# citizen_science_flora.net
KiCad netlist of a schematic drawn in EAGLE
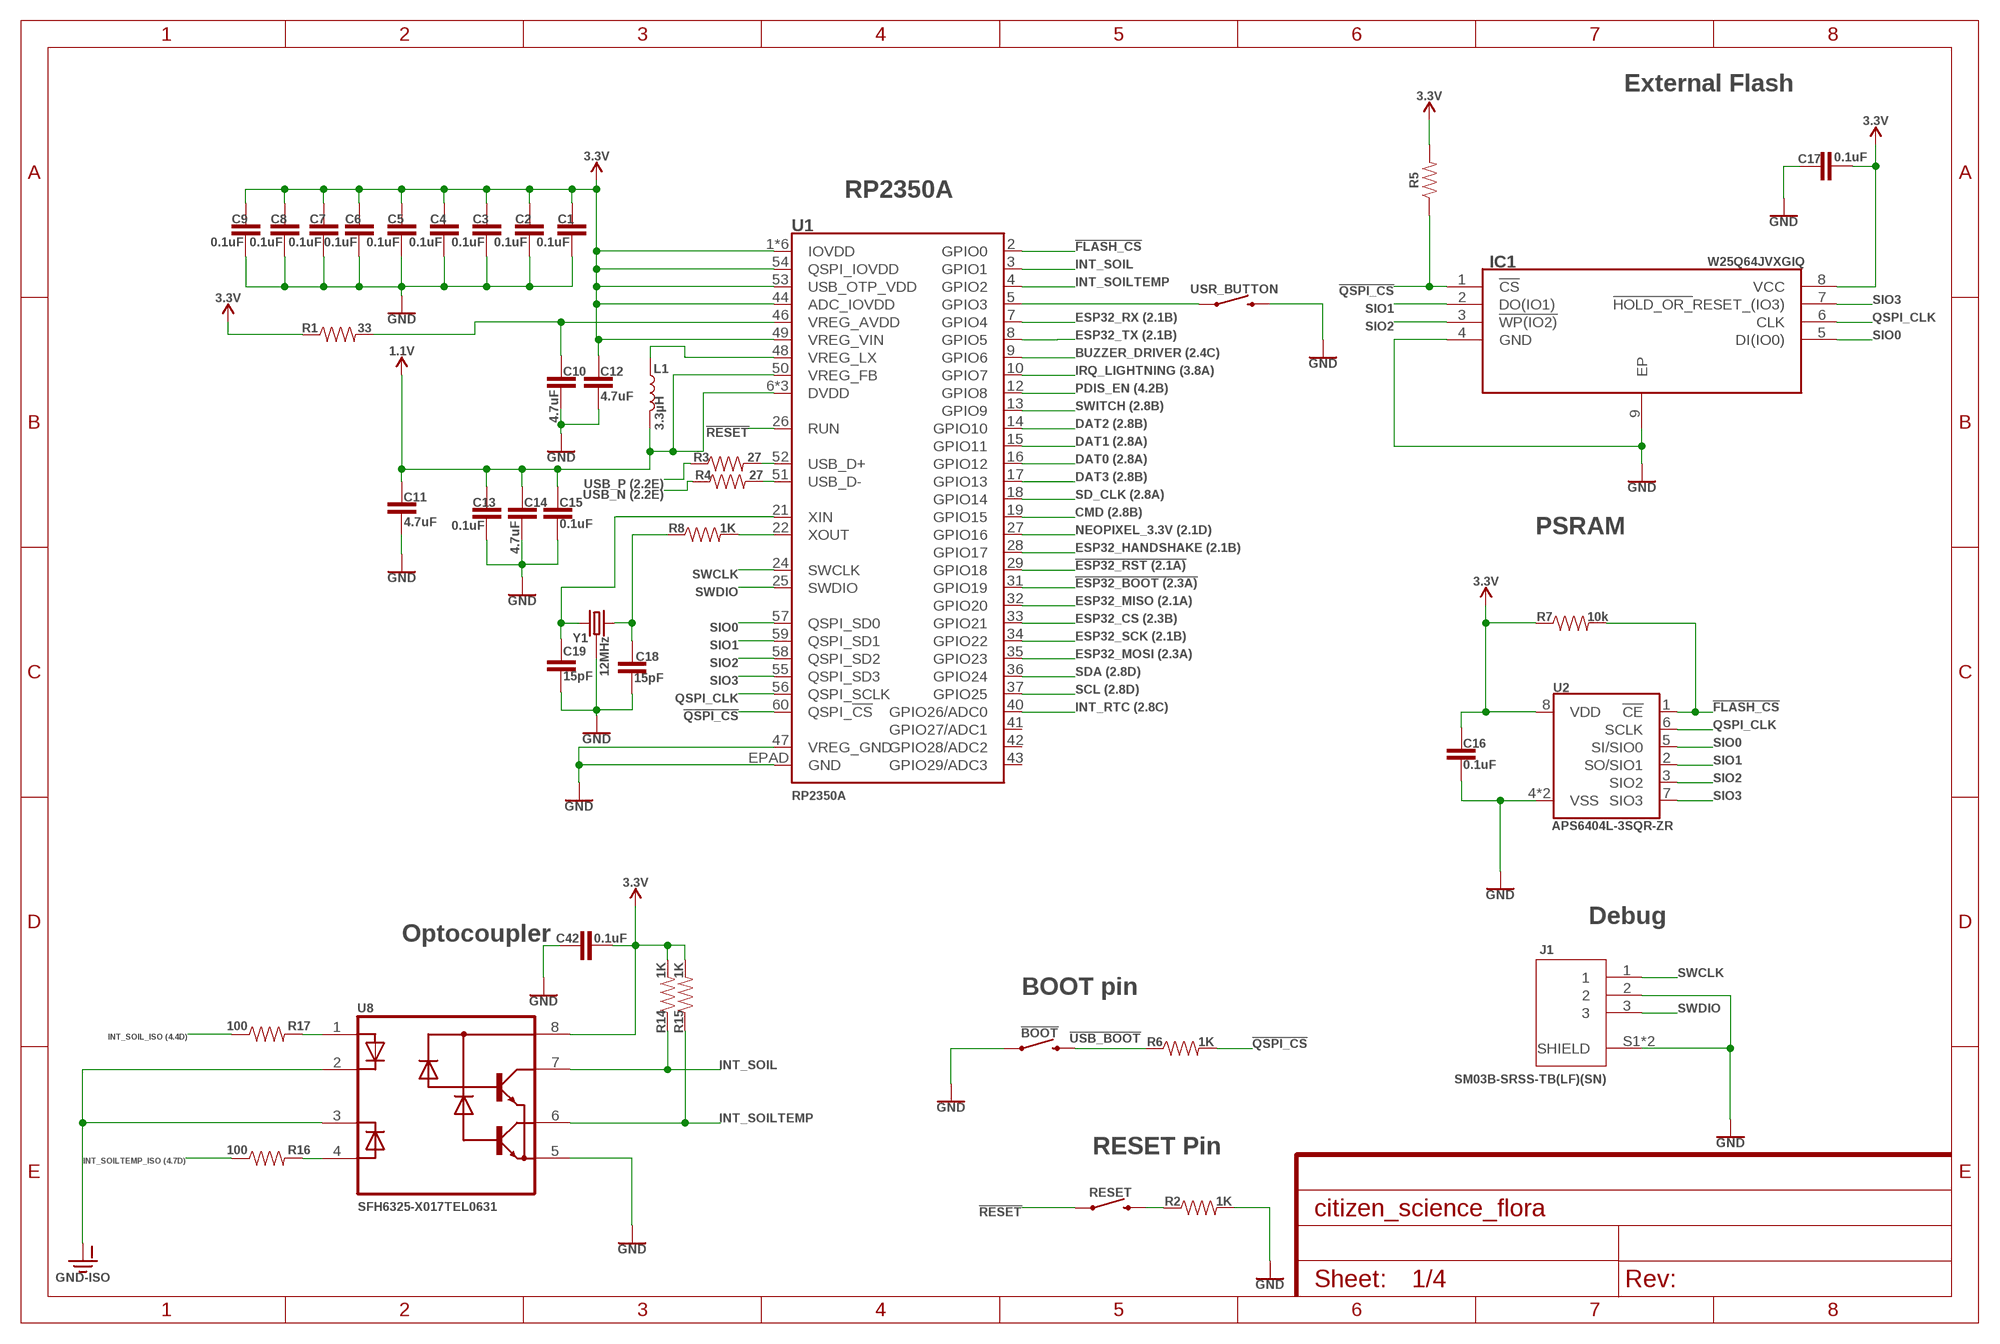
[diagram p0: schematic, sheet 1]
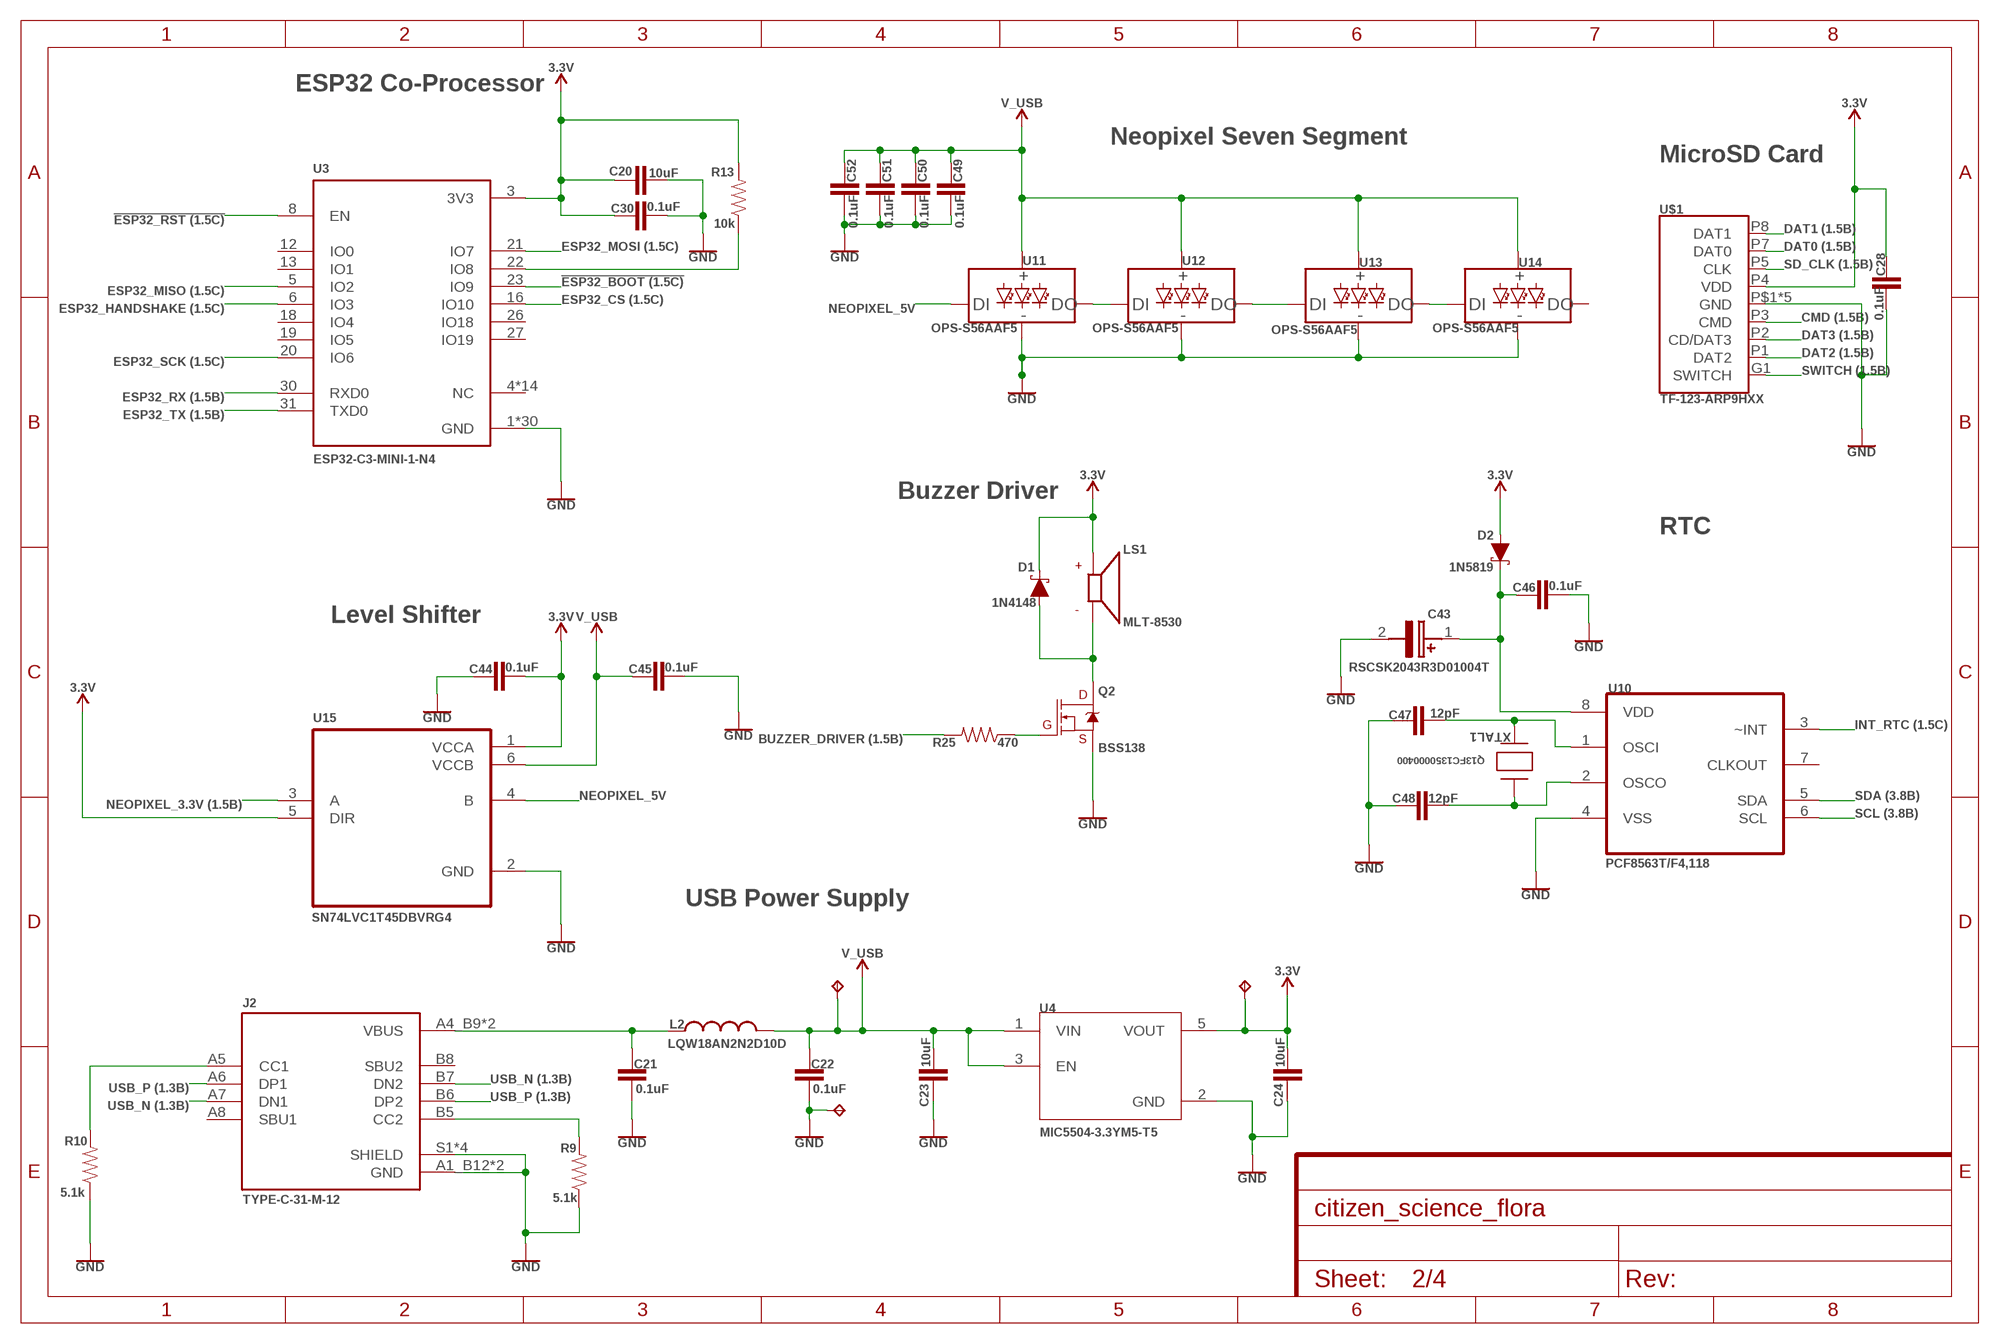
[diagram p1: schematic, sheet 2]
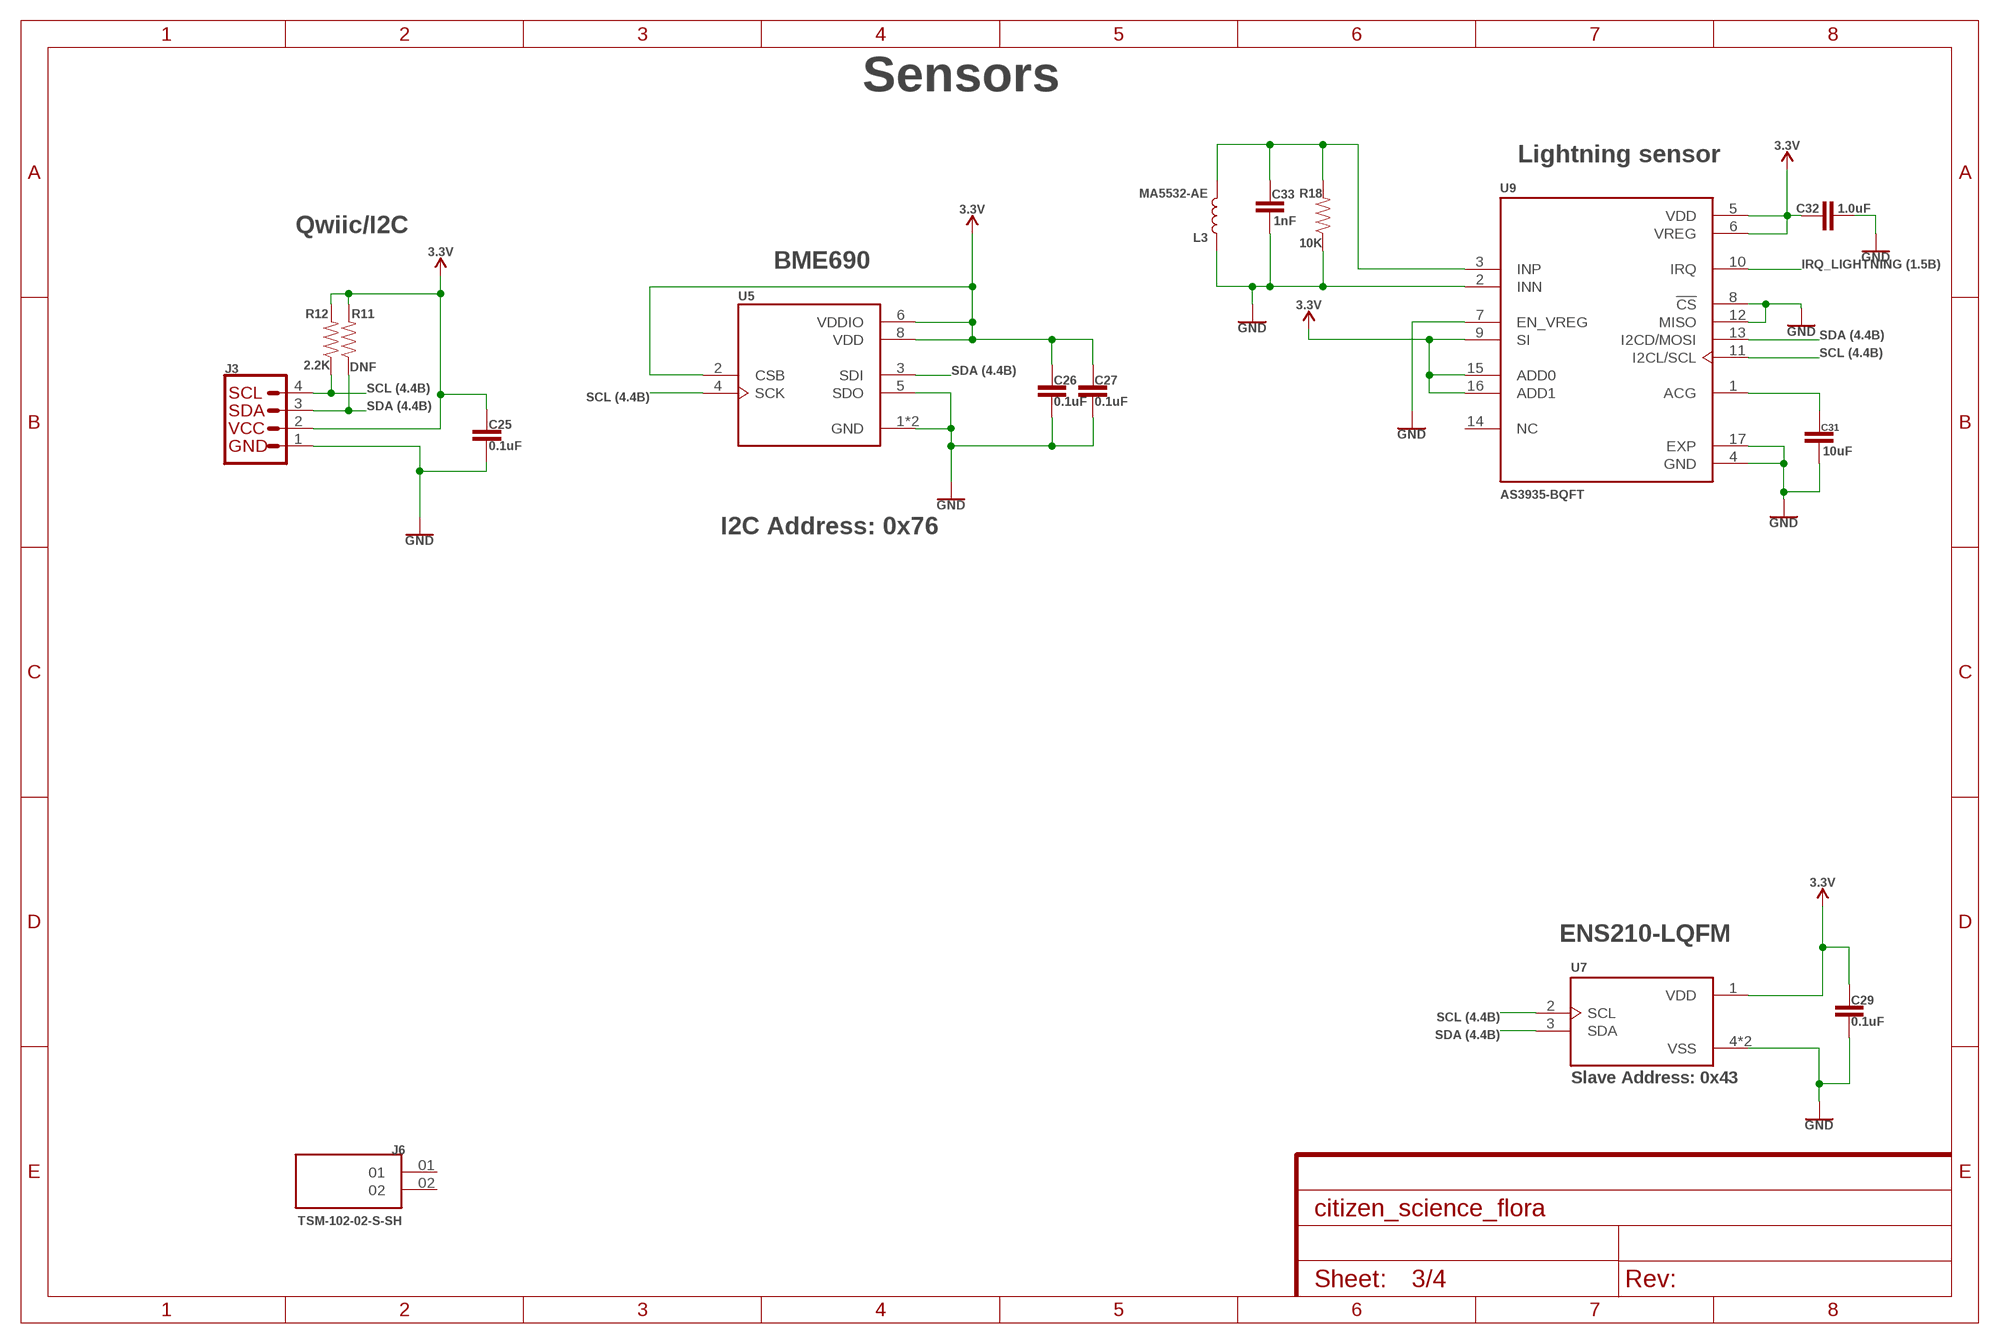
[diagram p2: schematic, sheet 3]
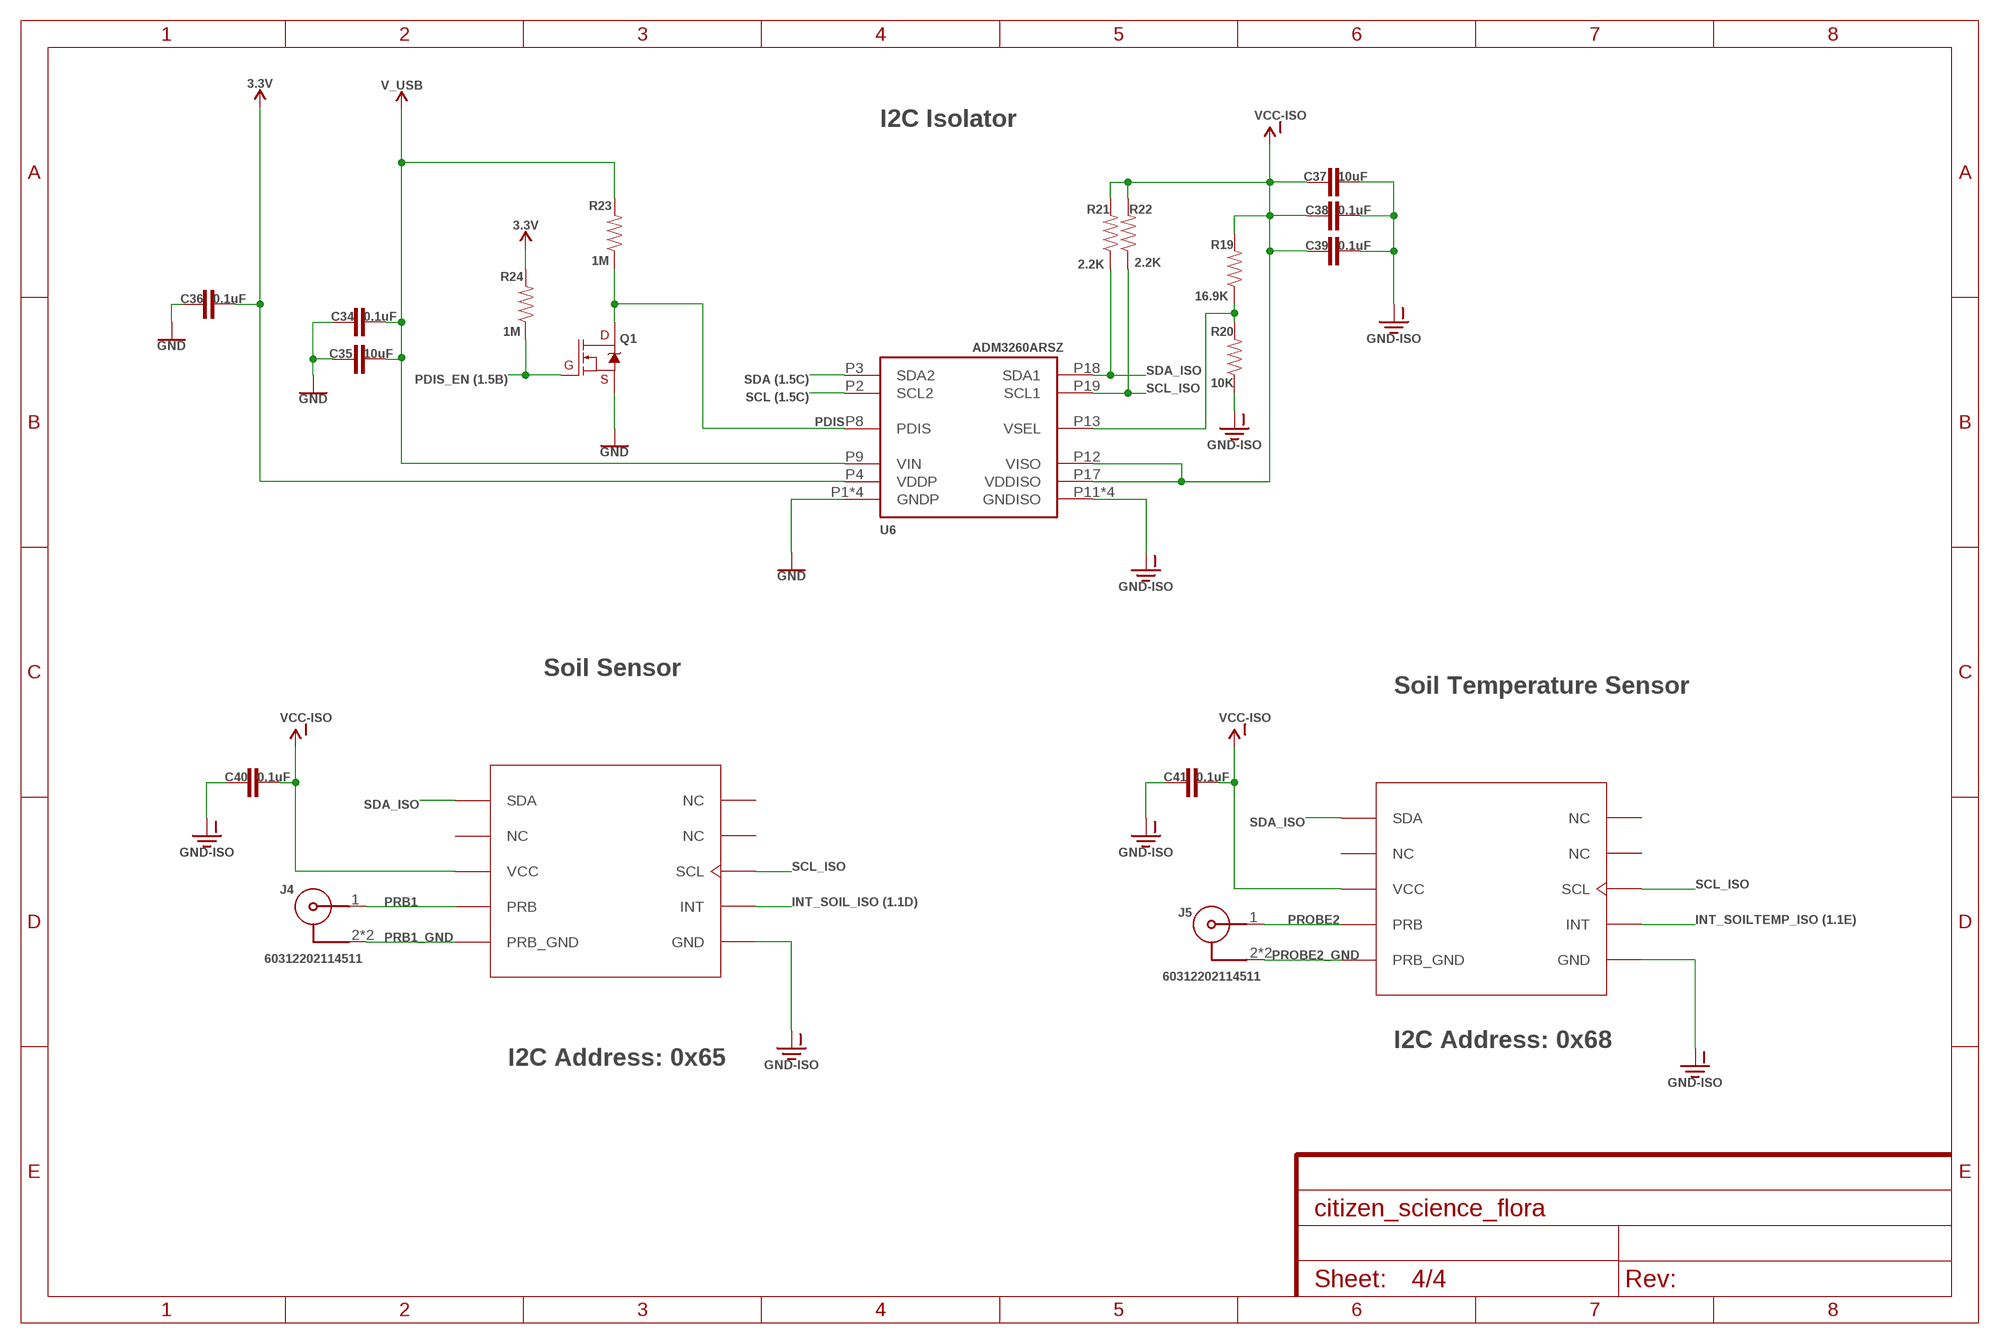
[diagram p3: schematic, sheet 4]

(export (version "E")
  (design (tool "Eeschema 10.0.6"))
  (components
    (comp (ref "!BOOT")
      (value "MOMENTARY-SWITCH-SPST-SMD-4.6X2.8MM")
      (footprint "eagle-import:TACTILE_SWITCH_SMD_4.6X2.8MM")
      (libsource (lib "eagle-import") (part "MOMENTARY-SWITCH-SPST-SMD-4.6X2.8MM"))
    )
    (comp (ref "C1")
      (value "0.1uF")
      (footprint "eagle-import:0402-TIGHT")
      (libsource (lib "eagle-import") (part "0.1UF-0402T-16V-10%-X7R-WE"))
    )
    (comp (ref "C2")
      (value "0.1uF")
      (footprint "eagle-import:0402-TIGHT")
      (libsource (lib "eagle-import") (part "0.1UF-0402T-16V-10%-X7R-WE"))
    )
    (comp (ref "C3")
      (value "0.1uF")
      (footprint "eagle-import:0402-TIGHT")
      (libsource (lib "eagle-import") (part "0.1UF-0402T-16V-10%-X7R-WE"))
    )
    (comp (ref "C4")
      (value "0.1uF")
      (footprint "eagle-import:0402-TIGHT")
      (libsource (lib "eagle-import") (part "0.1UF-0402T-16V-10%-X7R-WE"))
    )
    (comp (ref "C5")
      (value "0.1uF")
      (footprint "eagle-import:0402-TIGHT")
      (libsource (lib "eagle-import") (part "0.1UF-0402T-16V-10%-X7R-WE"))
    )
    (comp (ref "C6")
      (value "0.1uF")
      (footprint "eagle-import:0402-TIGHT")
      (libsource (lib "eagle-import") (part "0.1UF-0402T-16V-10%-X7R-WE"))
    )
    (comp (ref "C7")
      (value "0.1uF")
      (footprint "eagle-import:0402-TIGHT")
      (libsource (lib "eagle-import") (part "0.1UF-0402T-16V-10%-X7R-WE"))
    )
    (comp (ref "C8")
      (value "0.1uF")
      (footprint "eagle-import:0402-TIGHT")
      (libsource (lib "eagle-import") (part "0.1UF-0402T-16V-10%-X7R-WE"))
    )
    (comp (ref "C9")
      (value "0.1uF")
      (footprint "eagle-import:0402-TIGHT")
      (libsource (lib "eagle-import") (part "0.1UF-0402T-16V-10%-X7R-WE"))
    )
    (comp (ref "C10")
      (value "4.7uF")
      (footprint "eagle-import:0402-TIGHT")
      (libsource (lib "eagle-import") (part "4.7UF-0402_TIGHT-6.3V-20%-X5R"))
    )
    (comp (ref "C11")
      (value "4.7uF")
      (footprint "eagle-import:0402-TIGHT")
      (libsource (lib "eagle-import") (part "4.7UF-0402_TIGHT-6.3V-20%-X5R"))
    )
    (comp (ref "C12")
      (value "4.7uF")
      (footprint "eagle-import:0402-TIGHT")
      (libsource (lib "eagle-import") (part "4.7UF-0402_TIGHT-6.3V-20%-X5R"))
    )
    (comp (ref "C13")
      (value "0.1uF")
      (footprint "eagle-import:0402-TIGHT")
      (libsource (lib "eagle-import") (part "0.1UF-0402T-16V-10%-X7R-WE"))
    )
    (comp (ref "C14")
      (value "4.7uF")
      (footprint "eagle-import:0402-TIGHT")
      (libsource (lib "eagle-import") (part "4.7UF-0402_TIGHT-6.3V-20%-X5R"))
    )
    (comp (ref "C15")
      (value "0.1uF")
      (footprint "eagle-import:0402-TIGHT")
      (libsource (lib "eagle-import") (part "0.1UF-0402T-16V-10%-X7R-WE"))
    )
    (comp (ref "C16")
      (value "0.1uF")
      (footprint "eagle-import:0402-TIGHT")
      (libsource (lib "eagle-import") (part "0.1UF-0402T-16V-10%-X7R-WE"))
    )
    (comp (ref "C17")
      (value "0.1uF")
      (footprint "eagle-import:0402-TIGHT")
      (libsource (lib "eagle-import") (part "0.1UF-0402T-16V-10%-X7R-WE"))
    )
    (comp (ref "C18")
      (value "15pF")
      (footprint "eagle-import:0402")
      (libsource (lib "eagle-import") (part "15PF-0402-50V-5%"))
    )
    (comp (ref "C19")
      (value "15pF")
      (footprint "eagle-import:0402")
      (libsource (lib "eagle-import") (part "15PF-0402-50V-5%"))
    )
    (comp (ref "C42")
      (value "0.1uF")
      (footprint "eagle-import:0402-TIGHT")
      (libsource (lib "eagle-import") (part "0.1UF-0402T-16V-10%-X7R-WE"))
    )
    (comp (ref "IC1")
      (value "W25Q64JVXGIQ")
      (footprint "eagle-import:SON80P400X400X50-9N")
      (libsource (lib "eagle-import") (part "W25Q64JVXGIQ"))
    )
    (comp (ref "J1")
      (value "SM03B-SRSS-TB(LF)(SN)")
      (footprint "eagle-import:JST_SM03B-SRSS-TB(LF)(SN)")
      (fields (field (name "MF") "JST Sales America Inc."))
      (libsource (lib "eagle-import") (part "SM03B-SRSS-TB(LF)(SN)"))
    )
    (comp (ref "L1")
      (value "3.3µH")
      (footprint "eagle-import:0805")
      (libsource (lib "eagle-import") (part "INDUCTOR-0805-3.3UH"))
    )
    (comp (ref "R1")
      (value "33")
      (footprint "eagle-import:0402")
      (libsource (lib "eagle-import") (part "33OHM-0402-1/10W-1%"))
    )
    (comp (ref "R2")
      (value "1K")
      (footprint "eagle-import:0402")
      (libsource (lib "eagle-import") (part "1KOHM-0402-1/16W-1%"))
    )
    (comp (ref "R3")
      (value "27")
      (footprint "eagle-import:0402-TIGHT")
      (libsource (lib "eagle-import") (part "27OHM"))
    )
    (comp (ref "R4")
      (value "27")
      (footprint "eagle-import:0402-TIGHT")
      (libsource (lib "eagle-import") (part "27OHM"))
    )
    (comp (ref "R5")
      (value "RESISTOR0402")
      (footprint "eagle-import:0402")
      (libsource (lib "eagle-import") (part "RESISTOR0402"))
    )
    (comp (ref "R6")
      (value "1K")
      (footprint "eagle-import:0402")
      (libsource (lib "eagle-import") (part "1KOHM-0402-1/16W-1%"))
    )
    (comp (ref "R7")
      (value "10k")
      (footprint "eagle-import:0402")
      (libsource (lib "eagle-import") (part "10KOHM-0402-1/16W-1%"))
    )
    (comp (ref "R8")
      (value "1K")
      (footprint "eagle-import:0402")
      (libsource (lib "eagle-import") (part "1KOHM-0402-1/16W-1%"))
    )
    (comp (ref "R14")
      (value "1K")
      (footprint "eagle-import:0402")
      (libsource (lib "eagle-import") (part "1KOHM-0402-1/16W-1%"))
    )
    (comp (ref "R15")
      (value "1K")
      (footprint "eagle-import:0402")
      (libsource (lib "eagle-import") (part "1KOHM-0402-1/16W-1%"))
    )
    (comp (ref "R16")
      (value "100")
      (footprint "eagle-import:0402-TIGHT")
      (libsource (lib "eagle-import") (part "100OHM-0402-TIGHT-1/16W-1%"))
    )
    (comp (ref "R17")
      (value "100")
      (footprint "eagle-import:0402-TIGHT")
      (libsource (lib "eagle-import") (part "100OHM-0402-TIGHT-1/16W-1%"))
    )
    (comp (ref "RESET")
      (value "MOMENTARY-SWITCH-SPST-SMD-4.6X2.8MM")
      (footprint "eagle-import:TACTILE_SWITCH_SMD_4.6X2.8MM")
      (libsource (lib "eagle-import") (part "MOMENTARY-SWITCH-SPST-SMD-4.6X2.8MM"))
    )
    (comp (ref "U1")
      (value "RP2350A")
      (footprint "eagle-import:RP2350A")
      (libsource (lib "eagle-import") (part "RP2350A"))
    )
    (comp (ref "U2")
      (value "APS6404L-3SQR-ZR")
      (footprint "eagle-import:APS6404L-3SQR-ZR")
      (libsource (lib "eagle-import") (part "APS6404L-3SQR-ZR"))
    )
    (comp (ref "U8")
      (value "SFH6325-X017TEL0631")
      (footprint "eagle-import:SOIC127P599X175-8N")
      (libsource (lib "eagle-import") (part "SFH6325-X017TEL0631"))
    )
    (comp (ref "USR_BUTTON")
      (value "MOMENTARY-SWITCH-SPST-SMD-4.6X2.8MM")
      (footprint "eagle-import:TACTILE_SWITCH_SMD_4.6X2.8MM")
      (libsource (lib "eagle-import") (part "MOMENTARY-SWITCH-SPST-SMD-4.6X2.8MM"))
    )
    (comp (ref "Y1")
      (value "12MHz")
      (footprint "eagle-import:CRYSTAL-SMD-3.2X2.5MM")
      (libsource (lib "eagle-import") (part "CRYSTAL-GROUNDEDSMD-3.2X2.5"))
    )
    (comp (ref "C34")
      (value "0.1uF")
      (footprint "eagle-import:0402-TIGHT")
      (libsource (lib "eagle-import") (part "0.1UF-0402T-16V-10%-X7R-WE"))
    )
    (comp (ref "C35")
      (value "10uF")
      (footprint "eagle-import:0402-TIGHT")
      (libsource (lib "eagle-import") (part "10UF-0402T-6.3V-20%"))
    )
    (comp (ref "C36")
      (value "0.1uF")
      (footprint "eagle-import:0402-TIGHT")
      (libsource (lib "eagle-import") (part "0.1UF-0402T-16V-10%-X7R-WE"))
    )
    (comp (ref "C37")
      (value "10uF")
      (footprint "eagle-import:0402-TIGHT")
      (libsource (lib "eagle-import") (part "10UF-0402T-6.3V-20%"))
    )
    (comp (ref "C38")
      (value "0.1uF")
      (footprint "eagle-import:0402-TIGHT")
      (libsource (lib "eagle-import") (part "0.1UF-0402T-16V-10%-X7R-WE"))
    )
    (comp (ref "C39")
      (value "0.1uF")
      (footprint "eagle-import:0402-TIGHT")
      (libsource (lib "eagle-import") (part "0.1UF-0402T-16V-10%-X7R-WE"))
    )
    (comp (ref "C40")
      (value "0.1uF")
      (footprint "eagle-import:0402-TIGHT")
      (libsource (lib "eagle-import") (part "0.1UF-0402T-16V-10%-X7R-WE"))
    )
    (comp (ref "C41")
      (value "0.1uF")
      (footprint "eagle-import:0402-TIGHT")
      (libsource (lib "eagle-import") (part "0.1UF-0402T-16V-10%-X7R-WE"))
    )
    (comp (ref "J4")
      (value "60312202114511")
      (footprint "eagle-import:60312202114511")
      (fields (field (name "MF") "Wurth Electronics"))
      (libsource (lib "eagle-import") (part "60312202114511"))
    )
    (comp (ref "J5")
      (value "60312202114511")
      (footprint "eagle-import:60312202114511")
      (fields (field (name "MF") "Wurth Electronics"))
      (libsource (lib "eagle-import") (part "60312202114511"))
    )
    (comp (ref "Q1")
      (value "220mA/50V/3.5Ω")
      (footprint "eagle-import:SOT23-3")
      (libsource (lib "eagle-import") (part "MOSFET-NCH-BSS138"))
    )
    (comp (ref "R19")
      (value "16.9K")
      (footprint "eagle-import:0402")
      (libsource (lib "eagle-import") (part "RESISTOR0402"))
    )
    (comp (ref "R20")
      (value "10K")
      (footprint "eagle-import:0402-TIGHT")
      (libsource (lib "eagle-import") (part "10KOHM-0402-1/10W-0.1%"))
    )
    (comp (ref "R21")
      (value "2.2K")
      (footprint "eagle-import:0402")
      (libsource (lib "eagle-import") (part "2.2KOHM-0402-1/16W-1%"))
    )
    (comp (ref "R22")
      (value "2.2K")
      (footprint "eagle-import:0402")
      (libsource (lib "eagle-import") (part "2.2KOHM-0402-1/16W-1%"))
    )
    (comp (ref "R23")
      (value "1M")
      (footprint "eagle-import:0402")
      (libsource (lib "eagle-import") (part "1MOHM-0402-1/16W-5%"))
    )
    (comp (ref "R24")
      (value "1M")
      (footprint "eagle-import:0402")
      (libsource (lib "eagle-import") (part "1MOHM-0402-1/16W-5%"))
    )
    (comp (ref "U$2")
      (value "PH-OEM")
      (footprint "eagle-import:PH_SENSOR")
      (libsource (lib "eagle-import") (part "PH-OEM"))
    )
    (comp (ref "U$3")
      (value "PH-OEM")
      (footprint "eagle-import:PH_SENSOR")
      (libsource (lib "eagle-import") (part "PH-OEM"))
    )
    (comp (ref "U6")
      (value "ADM3260ARSZ")
      (footprint "eagle-import:SSOP20")
      (fields (field (name "MF") "Analog Devices"))
      (libsource (lib "eagle-import") (part "ADM3260ARSZ"))
    )
    (comp (ref "3.3V")
      (value "TPB1,27")
      (footprint "eagle-import:B1,27")
      (libsource (lib "eagle-import") (part "TPB1,27"))
    )
    (comp (ref "C20")
      (value "10uF")
      (footprint "eagle-import:0402-TIGHT")
      (libsource (lib "eagle-import") (part "10UF-0402T-6.3V-20%"))
    )
    (comp (ref "C21")
      (value "0.1uF")
      (footprint "eagle-import:0402")
      (libsource (lib "eagle-import") (part "0.1UF-0402-6.3V-10%-X7R"))
    )
    (comp (ref "C22")
      (value "0.1uF")
      (footprint "eagle-import:0402")
      (libsource (lib "eagle-import") (part "0.1UF-0402-6.3V-10%-X7R"))
    )
    (comp (ref "C23")
      (value "10uF")
      (footprint "eagle-import:0402-TIGHT")
      (libsource (lib "eagle-import") (part "10UF-0402T-6.3V-20%"))
    )
    (comp (ref "C24")
      (value "10uF")
      (footprint "eagle-import:0402-TIGHT")
      (libsource (lib "eagle-import") (part "10UF-0402T-6.3V-20%"))
    )
    (comp (ref "C28")
      (value "0.1uF")
      (footprint "eagle-import:0402-TIGHT")
      (libsource (lib "eagle-import") (part "0.1UF-0402T-16V-10%-X7R-WE"))
    )
    (comp (ref "C30")
      (value "0.1uF")
      (footprint "eagle-import:0402")
      (libsource (lib "eagle-import") (part "0.1UF-0402-6.3V-10%-X7R"))
    )
    (comp (ref "C43")
      (value "RSCSK2043R3D01004T")
      (footprint "eagle-import:RSCSK2043R3D01004T")
      (fields (field (name "MOUSER_PART_NUMBER") "555-DSK3R3H204T614H2"))
      (libsource (lib "eagle-import") (part "RSCSK2043R3D01004T"))
    )
    (comp (ref "C44")
      (value "0.1uF")
      (footprint "eagle-import:0402")
      (libsource (lib "eagle-import") (part "0.1UF-0402-6.3V-10%-X7R"))
    )
    (comp (ref "C45")
      (value "0.1uF")
      (footprint "eagle-import:0402")
      (libsource (lib "eagle-import") (part "0.1UF-0402-6.3V-10%-X7R"))
    )
    (comp (ref "C46")
      (value "0.1uF")
      (footprint "eagle-import:0402")
      (libsource (lib "eagle-import") (part "0.1UF-0402-6.3V-10%-X7R"))
    )
    (comp (ref "C47")
      (value "12pF")
      (footprint "eagle-import:0402")
      (libsource (lib "eagle-import") (part "12PF-0402-50V-5%"))
    )
    (comp (ref "C48")
      (value "12pF")
      (footprint "eagle-import:0402")
      (libsource (lib "eagle-import") (part "12PF-0402-50V-5%"))
    )
    (comp (ref "C49")
      (value "0.1uF")
      (footprint "eagle-import:0402")
      (libsource (lib "eagle-import") (part "0.1UF-0402-6.3V-10%-X7R"))
    )
    (comp (ref "C50")
      (value "0.1uF")
      (footprint "eagle-import:0402")
      (libsource (lib "eagle-import") (part "0.1UF-0402-6.3V-10%-X7R"))
    )
    (comp (ref "C51")
      (value "0.1uF")
      (footprint "eagle-import:0402")
      (libsource (lib "eagle-import") (part "0.1UF-0402-6.3V-10%-X7R"))
    )
    (comp (ref "C52")
      (value "0.1uF")
      (footprint "eagle-import:0402")
      (libsource (lib "eagle-import") (part "0.1UF-0402-6.3V-10%-X7R"))
    )
    (comp (ref "D1")
      (value "1N4148")
      (footprint "eagle-import:SOD-323")
      (libsource (lib "eagle-import") (part "DIODE-SCHOTTKY-BAT60A"))
    )
    (comp (ref "D2")
      (value "1N5819")
      (footprint "eagle-import:SOD-323")
      (libsource (lib "eagle-import") (part "DIODE-SCHOTTKY-BAT20J"))
    )
    (comp (ref "GND")
      (value "TPB1,27")
      (footprint "eagle-import:B1,27")
      (libsource (lib "eagle-import") (part "TPB1,27"))
    )
    (comp (ref "J2")
      (value "TYPE-C-31-M-12")
      (footprint "eagle-import:HRO_TYPE-C-31-M-12")
      (fields (field (name "MF") "HRO Electronics Co., Ltd."))
      (libsource (lib "eagle-import") (part "TYPE-C-31-M-12"))
    )
    (comp (ref "L2")
      (value "LQW18AN2N2D10D")
      (footprint "eagle-import:INDC1608X100N")
      (fields (field (name "MF") "Murata"))
      (libsource (lib "eagle-import") (part "LQW18AN2N2D10D"))
    )
    (comp (ref "LS1")
      (value "MLT-8530")
      (footprint "eagle-import:XDCR_CMT-8504-100-SMT-TR")
      (fields (field (name "MANUFACTURER") "CUI Inc."))
      (libsource (lib "eagle-import") (part "CMT-8504-100-SMT-TR"))
    )
    (comp (ref "Q2")
      (value "BSS138")
      (footprint "eagle-import:SOT323")
      (libsource (lib "eagle-import") (part "MOSFET-NCH-2N7002PW"))
    )
    (comp (ref "R9")
      (value "5.1k")
      (footprint "eagle-import:0402")
      (libsource (lib "eagle-import") (part "5.1KOHM-0402-1/16W-1%"))
    )
    (comp (ref "R10")
      (value "5.1k")
      (footprint "eagle-import:0402")
      (libsource (lib "eagle-import") (part "5.1KOHM-0402-1/16W-1%"))
    )
    (comp (ref "R13")
      (value "10k")
      (footprint "eagle-import:0402")
      (libsource (lib "eagle-import") (part "10KOHM-0402-1/16W-1%"))
    )
    (comp (ref "R25")
      (value "470")
      (footprint "eagle-import:0402")
      (libsource (lib "eagle-import") (part "10KOHM-0402-1/16W-1%"))
    )
    (comp (ref "U$1")
      (value "TF-123-ARP9HXX")
      (footprint "eagle-import:MICROSDCARD")
      (libsource (lib "eagle-import") (part "TF-123-ARP9HXX"))
    )
    (comp (ref "U3")
      (value "ESP32-C3-MINI-1-N4")
      (footprint "eagle-import:XCVR_ESP32-C3-MINI-1-N4")
      (fields (field (name "MF") "Espressif Systems"))
      (libsource (lib "eagle-import") (part "ESP32-C3-MINI-1-N4"))
    )
    (comp (ref "U4")
      (value "MIC5504-3.3YM5-T5")
      (footprint "eagle-import:SOT95P280X145-5N")
      (fields (field (name "MF") "Microchip"))
      (libsource (lib "eagle-import") (part "MIC5504-3.3YM5-T5"))
    )
    (comp (ref "U10")
      (value "PCF8563T/F4,118")
      (footprint "eagle-import:SOIC127P600X175-8N")
      (fields (field (name "MF") "NXP USA"))
      (libsource (lib "eagle-import") (part "PCF8563T/F4,118"))
    )
    (comp (ref "U11")
      (value "OPS-S56AAF5")
      (footprint "eagle-import:OPS-S56AAF5")
      (libsource (lib "eagle-import") (part "OPS-S56AAF5"))
    )
    (comp (ref "U12")
      (value "OPS-S56AAF5")
      (footprint "eagle-import:OPS-S56AAF5")
      (libsource (lib "eagle-import") (part "OPS-S56AAF5"))
    )
    (comp (ref "U13")
      (value "OPS-S56AAF5")
      (footprint "eagle-import:OPS-S56AAF5")
      (libsource (lib "eagle-import") (part "OPS-S56AAF5"))
    )
    (comp (ref "U14")
      (value "OPS-S56AAF5")
      (footprint "eagle-import:OPS-S56AAF5")
      (libsource (lib "eagle-import") (part "OPS-S56AAF5"))
    )
    (comp (ref "U15")
      (value "SN74LVC1T45DBVRG4")
      (footprint "eagle-import:SOT95P280X145-6N")
      (fields (field (name "MF") "Texas Instruments"))
      (libsource (lib "eagle-import") (part "SN74LVC1T45DBVRG4"))
    )
    (comp (ref "USB")
      (value "V_USB")
      (footprint "eagle-import:B1,27")
      (libsource (lib "eagle-import") (part "TPB1,27"))
    )
    (comp (ref "XTAL1")
      (value "Q13FC1350000400")
      (footprint "eagle-import:XTAL_FC-135_EPS")
      (fields (field (name "MF") "EPSON"))
      (libsource (lib "eagle-import") (part "Q13FC1350000400"))
    )
    (comp (ref "C25")
      (value "0.1uF")
      (footprint "eagle-import:0402-TIGHT")
      (libsource (lib "eagle-import") (part "0.1UF-0402T-16V-10%-X7R-WE"))
    )
    (comp (ref "C26")
      (value "0.1uF")
      (footprint "eagle-import:0402-TIGHT")
      (libsource (lib "eagle-import") (part "0.1UF-0402T-16V-10%-X7R-WE"))
    )
    (comp (ref "C27")
      (value "0.1uF")
      (footprint "eagle-import:0402-TIGHT")
      (libsource (lib "eagle-import") (part "0.1UF-0402T-16V-10%-X7R-WE"))
    )
    (comp (ref "C29")
      (value "0.1uF")
      (footprint "eagle-import:0402-TIGHT")
      (libsource (lib "eagle-import") (part "0.1UF-0402T-16V-10%-X7R-WE"))
    )
    (comp (ref "C31")
      (value "10uF")
      (footprint "eagle-import:0402-TIGHT")
      (libsource (lib "eagle-import") (part "10UF-0402T-6.3V-20%"))
    )
    (comp (ref "C32")
      (value "1.0uF")
      (footprint "eagle-import:0402")
      (libsource (lib "eagle-import") (part "1.0UF-0402-16V-10%"))
    )
    (comp (ref "C33")
      (value "1nF")
      (footprint "eagle-import:0402")
      (libsource (lib "eagle-import") (part "1.0NF/1000PF-0402-25V-10%-X7R"))
    )
    (comp (ref "J3")
      (value "QWIIC_CONNECTORJS-1MM")
      (footprint "eagle-import:1X04_1MM_RA")
      (libsource (lib "eagle-import") (part "QWIIC_CONNECTORJS-1MM"))
    )
    (comp (ref "J6")
      (value "TSM-102-02-S-SH")
      (footprint "eagle-import:SAMTEC_TSM-102-02-S-SH")
      (fields (field (name "MF") "Samtec"))
      (libsource (lib "eagle-import") (part "TSM-102-02-S-SH"))
    )
    (comp (ref "L3")
      (value "MA5532-AE")
      (footprint "eagle-import:MA5532-AE")
      (fields (field (name "MF") "Coilcraft"))
      (libsource (lib "eagle-import") (part "MA5532-AE"))
    )
    (comp (ref "R11")
      (value "DNF")
      (footprint "eagle-import:0402")
      (libsource (lib "eagle-import") (part "2.2KOHM-0402-1/16W-1%"))
    )
    (comp (ref "R12")
      (value "2.2K")
      (footprint "eagle-import:0402")
      (libsource (lib "eagle-import") (part "2.2KOHM-0402-1/16W-1%"))
    )
    (comp (ref "R18")
      (value "10K")
      (footprint "eagle-import:0402-TIGHT")
      (libsource (lib "eagle-import") (part "10KOHM-0402-1/10W-0.1%"))
    )
    (comp (ref "U5")
      (value "BME690")
      (footprint "eagle-import:IC_BME688")
      (fields (field (name "MF") "Bosch Sensortec") (field (name "MP") "BME688"))
      (libsource (lib "eagle-import") (part "BME690"))
    )
    (comp (ref "U7")
      (value "ENS210-LQFM")
      (footprint "eagle-import:XDCR_ENS210-LQFM")
      (fields (field (name "MF") "ScioSense"))
      (libsource (lib "eagle-import") (part "ENS210-LQFM"))
    )
    (comp (ref "U9")
      (value "AS3935-BQFT")
      (footprint "eagle-import:QFN65P400X400X80-17N")
      (fields (field (name "MF") "ScioSense"))
      (libsource (lib "eagle-import") (part "AS3935-BQFT"))
    )
  )
  (nets
    (net (code "1") (name "1.1V") (class "Default")
      (node (ref "C11") (pin "1") (pinfunction "1_1") (pintype "passive"))
      (node (ref "C13") (pin "1") (pinfunction "1_1") (pintype "passive"))
      (node (ref "C14") (pin "1") (pinfunction "1_1") (pintype "passive"))
      (node (ref "C15") (pin "1") (pinfunction "1_1") (pintype "passive"))
      (node (ref "L1") (pin "2") (pinfunction "2_2") (pintype "passive"))
      (node (ref "U1") (pin "23") (pinfunction "DVDD_23") (pintype "bidirectional"))
      (node (ref "U1") (pin "39") (pinfunction "DVDD_39") (pintype "bidirectional"))
      (node (ref "U1") (pin "50") (pinfunction "VREG_FB_50") (pintype "bidirectional"))
      (node (ref "U1") (pin "6") (pinfunction "DVDD_6") (pintype "bidirectional"))
    )
    (net (code "2") (name "3.3V") (class "Default")
      (node (ref "3.3V") (pin "TP") (pinfunction "TP_TP") (pintype "input"))
      (node (ref "C1") (pin "1") (pinfunction "1_1") (pintype "passive"))
      (node (ref "C12") (pin "1") (pinfunction "1_1") (pintype "passive"))
      (node (ref "C16") (pin "1") (pinfunction "1_1") (pintype "passive"))
      (node (ref "C17") (pin "2") (pinfunction "2_2") (pintype "passive"))
      (node (ref "C2") (pin "1") (pinfunction "1_1") (pintype "passive"))
      (node (ref "C20") (pin "1") (pinfunction "1_1") (pintype "passive"))
      (node (ref "C24") (pin "2") (pinfunction "2_2") (pintype "passive"))
      (node (ref "C25") (pin "1") (pinfunction "1_1") (pintype "passive"))
      (node (ref "C26") (pin "1") (pinfunction "1_1") (pintype "passive"))
      (node (ref "C27") (pin "1") (pinfunction "1_1") (pintype "passive"))
      (node (ref "C28") (pin "1") (pinfunction "1_1") (pintype "passive"))
      (node (ref "C29") (pin "1") (pinfunction "1_1") (pintype "passive"))
      (node (ref "C3") (pin "1") (pinfunction "1_1") (pintype "passive"))
      (node (ref "C30") (pin "1") (pinfunction "1_1") (pintype "passive"))
      (node (ref "C32") (pin "1") (pinfunction "1_1") (pintype "passive"))
      (node (ref "C36") (pin "2") (pinfunction "2_2") (pintype "passive"))
      (node (ref "C4") (pin "1") (pinfunction "1_1") (pintype "passive"))
      (node (ref "C42") (pin "2") (pinfunction "2_2") (pintype "passive"))
      (node (ref "C44") (pin "2") (pinfunction "2_2") (pintype "passive"))
      (node (ref "C5") (pin "1") (pinfunction "1_1") (pintype "passive"))
      (node (ref "C6") (pin "1") (pinfunction "1_1") (pintype "passive"))
      (node (ref "C7") (pin "1") (pinfunction "1_1") (pintype "passive"))
      (node (ref "C8") (pin "1") (pinfunction "1_1") (pintype "passive"))
      (node (ref "C9") (pin "1") (pinfunction "1_1") (pintype "passive"))
      (node (ref "D1") (pin "C") (pinfunction "C_C") (pintype "passive"))
      (node (ref "D2") (pin "A") (pinfunction "A_A") (pintype "passive"))
      (node (ref "IC1") (pin "8") (pinfunction "VCC_8") (pintype "bidirectional"))
      (node (ref "J3") (pin "2") (pinfunction "2_2") (pintype "power_in"))
      (node (ref "LS1") (pin "P") (pinfunction "P_P") (pintype "passive"))
      (node (ref "R1") (pin "1") (pinfunction "1_1") (pintype "passive"))
      (node (ref "R11") (pin "2") (pinfunction "2_2") (pintype "passive"))
      (node (ref "R12") (pin "2") (pinfunction "2_2") (pintype "passive"))
      (node (ref "R13") (pin "2") (pinfunction "2_2") (pintype "passive"))
      (node (ref "R14") (pin "2") (pinfunction "2_2") (pintype "passive"))
      (node (ref "R15") (pin "2") (pinfunction "2_2") (pintype "passive"))
      (node (ref "R24") (pin "2") (pinfunction "2_2") (pintype "passive"))
      (node (ref "R5") (pin "2") (pinfunction "2_2") (pintype "passive"))
      (node (ref "R7") (pin "1") (pinfunction "1_1") (pintype "passive"))
      (node (ref "U$1") (pin "P4") (pinfunction "VDD_P4") (pintype "power_in"))
      (node (ref "U1") (pin "1") (pinfunction "IOVDD_1") (pintype "bidirectional"))
      (node (ref "U1") (pin "11") (pinfunction "IOVDD_11") (pintype "bidirectional"))
      (node (ref "U1") (pin "20") (pinfunction "IOVDD_20") (pintype "bidirectional"))
      (node (ref "U1") (pin "30") (pinfunction "IOVDD_30") (pintype "bidirectional"))
      (node (ref "U1") (pin "38") (pinfunction "IOVDD_38") (pintype "bidirectional"))
      (node (ref "U1") (pin "44") (pinfunction "ADC_IOVDD_44") (pintype "bidirectional"))
      (node (ref "U1") (pin "45") (pinfunction "IOVDD_45") (pintype "bidirectional"))
      (node (ref "U1") (pin "49") (pinfunction "VREG_VIN_49") (pintype "bidirectional"))
      (node (ref "U1") (pin "53") (pinfunction "USB_OTP_VDD_53") (pintype "bidirectional"))
      (node (ref "U1") (pin "54") (pinfunction "QSPI_IOVDD_54") (pintype "bidirectional"))
      (node (ref "U15") (pin "1") (pinfunction "VCCA_1") (pintype "power_in"))
      (node (ref "U15") (pin "5") (pinfunction "DIR_5") (pintype "input"))
      (node (ref "U2") (pin "8") (pinfunction "VDD_8") (pintype "bidirectional"))
      (node (ref "U3") (pin "3") (pinfunction "3V3_3") (pintype "power_in"))
      (node (ref "U4") (pin "5") (pinfunction "VOUT_5") (pintype "output"))
      (node (ref "U5") (pin "2") (pinfunction "CSB_2") (pintype "input"))
      (node (ref "U5") (pin "6") (pinfunction "VDDIO_6") (pintype "power_in"))
      (node (ref "U5") (pin "8") (pinfunction "VDD_8") (pintype "power_in"))
      (node (ref "U6") (pin "P4") (pinfunction "VDDP_P4") (pintype "bidirectional"))
      (node (ref "U7") (pin "1") (pinfunction "VDD_1") (pintype "power_in"))
      (node (ref "U8") (pin "8") (pinfunction "C(VCC)_8") (pintype "passive"))
      (node (ref "U9") (pin "15") (pinfunction "ADD0_15") (pintype "input"))
      (node (ref "U9") (pin "16") (pinfunction "ADD1_16") (pintype "input"))
      (node (ref "U9") (pin "5") (pinfunction "VDD_5") (pintype "power_in"))
      (node (ref "U9") (pin "6") (pinfunction "VREG_6") (pintype "power_in"))
      (node (ref "U9") (pin "9") (pinfunction "SI_9") (pintype "input"))
    )
    (net (code "3") (name "BUZZER_DRIVER") (class "Default")
      (node (ref "R25") (pin "2") (pinfunction "2_2") (pintype "passive"))
      (node (ref "U1") (pin "9") (pinfunction "GPIO6_9") (pintype "bidirectional"))
    )
    (net (code "4") (name "CMD") (class "Default")
      (node (ref "U$1") (pin "P3") (pinfunction "CMD_P3") (pintype "bidirectional"))
      (node (ref "U1") (pin "19") (pinfunction "GPIO15_19") (pintype "bidirectional"))
    )
    (net (code "5") (name "DAT0") (class "Default")
      (node (ref "U$1") (pin "P7") (pinfunction "DAT0_P7") (pintype "bidirectional"))
      (node (ref "U1") (pin "16") (pinfunction "GPIO12_16") (pintype "bidirectional"))
    )
    (net (code "6") (name "DAT1") (class "Default")
      (node (ref "U$1") (pin "P8") (pinfunction "DAT1_P8") (pintype "bidirectional"))
      (node (ref "U1") (pin "15") (pinfunction "GPIO11_15") (pintype "bidirectional"))
    )
    (net (code "7") (name "DAT2") (class "Default")
      (node (ref "U$1") (pin "P1") (pinfunction "DAT2_P1") (pintype "bidirectional"))
      (node (ref "U1") (pin "14") (pinfunction "GPIO10_14") (pintype "bidirectional"))
    )
    (net (code "8") (name "DAT3") (class "Default")
      (node (ref "U$1") (pin "P2") (pinfunction "CD/DAT3_P2") (pintype "bidirectional"))
      (node (ref "U1") (pin "17") (pinfunction "GPIO13_17") (pintype "bidirectional"))
    )
    (net (code "9") (name "ESP32_CS") (class "Default")
      (node (ref "U1") (pin "33") (pinfunction "GPIO21_33") (pintype "bidirectional"))
      (node (ref "U3") (pin "16") (pinfunction "IO10_16") (pintype "bidirectional"))
    )
    (net (code "10") (name "ESP32_HANDSHAKE") (class "Default")
      (node (ref "U1") (pin "28") (pinfunction "GPIO17_28") (pintype "bidirectional"))
      (node (ref "U3") (pin "6") (pinfunction "IO3_6") (pintype "bidirectional"))
    )
    (net (code "11") (name "ESP32_MISO") (class "Default")
      (node (ref "U1") (pin "32") (pinfunction "GPIO20_32") (pintype "bidirectional"))
      (node (ref "U3") (pin "5") (pinfunction "IO2_5") (pintype "bidirectional"))
    )
    (net (code "12") (name "ESP32_MOSI") (class "Default")
      (node (ref "U1") (pin "35") (pinfunction "GPIO23_35") (pintype "bidirectional"))
      (node (ref "U3") (pin "21") (pinfunction "IO7_21") (pintype "bidirectional"))
    )
    (net (code "13") (name "ESP32_RX") (class "Default")
      (node (ref "U1") (pin "7") (pinfunction "GPIO4_7") (pintype "bidirectional"))
      (node (ref "U3") (pin "30") (pinfunction "RXD0_30") (pintype "bidirectional"))
    )
    (net (code "14") (name "ESP32_SCK") (class "Default")
      (node (ref "U1") (pin "34") (pinfunction "GPIO22_34") (pintype "bidirectional"))
      (node (ref "U3") (pin "20") (pinfunction "IO6_20") (pintype "bidirectional"))
    )
    (net (code "15") (name "ESP32_TX") (class "Default")
      (node (ref "U1") (pin "8") (pinfunction "GPIO5_8") (pintype "bidirectional"))
      (node (ref "U3") (pin "31") (pinfunction "TXD0_31") (pintype "bidirectional"))
    )
    (net (code "16") (name "GND") (class "Default")
      (node (ref "!BOOT") (pin "1") (pinfunction "1_1") (pintype "passive"))
      (node (ref "!BOOT") (pin "2") (pinfunction "1_2") (pintype "passive"))
      (node (ref "C1") (pin "2") (pinfunction "2_2") (pintype "passive"))
      (node (ref "C10") (pin "2") (pinfunction "2_2") (pintype "passive"))
      (node (ref "C11") (pin "2") (pinfunction "2_2") (pintype "passive"))
      (node (ref "C12") (pin "2") (pinfunction "2_2") (pintype "passive"))
      (node (ref "C13") (pin "2") (pinfunction "2_2") (pintype "passive"))
      (node (ref "C14") (pin "2") (pinfunction "2_2") (pintype "passive"))
      (node (ref "C15") (pin "2") (pinfunction "2_2") (pintype "passive"))
      (node (ref "C16") (pin "2") (pinfunction "2_2") (pintype "passive"))
      (node (ref "C17") (pin "1") (pinfunction "1_1") (pintype "passive"))
      (node (ref "C18") (pin "2") (pinfunction "2_2") (pintype "passive"))
      (node (ref "C19") (pin "2") (pinfunction "2_2") (pintype "passive"))
      (node (ref "C2") (pin "2") (pinfunction "2_2") (pintype "passive"))
      (node (ref "C20") (pin "2") (pinfunction "2_2") (pintype "passive"))
      (node (ref "C21") (pin "2") (pinfunction "2_2") (pintype "passive"))
      (node (ref "C22") (pin "2") (pinfunction "2_2") (pintype "passive"))
      (node (ref "C23") (pin "1") (pinfunction "1_1") (pintype "passive"))
      (node (ref "C24") (pin "1") (pinfunction "1_1") (pintype "passive"))
      (node (ref "C25") (pin "2") (pinfunction "2_2") (pintype "passive"))
      (node (ref "C26") (pin "2") (pinfunction "2_2") (pintype "passive"))
      (node (ref "C27") (pin "2") (pinfunction "2_2") (pintype "passive"))
      (node (ref "C28") (pin "2") (pinfunction "2_2") (pintype "passive"))
      (node (ref "C29") (pin "2") (pinfunction "2_2") (pintype "passive"))
      (node (ref "C3") (pin "2") (pinfunction "2_2") (pintype "passive"))
      (node (ref "C30") (pin "2") (pinfunction "2_2") (pintype "passive"))
      (node (ref "C31") (pin "2") (pinfunction "2_2") (pintype "passive"))
      (node (ref "C32") (pin "2") (pinfunction "2_2") (pintype "passive"))
      (node (ref "C33") (pin "2") (pinfunction "2_2") (pintype "passive"))
      (node (ref "C34") (pin "1") (pinfunction "1_1") (pintype "passive"))
      (node (ref "C35") (pin "1") (pinfunction "1_1") (pintype "passive"))
      (node (ref "C36") (pin "1") (pinfunction "1_1") (pintype "passive"))
      (node (ref "C4") (pin "2") (pinfunction "2_2") (pintype "passive"))
      (node (ref "C42") (pin "1") (pinfunction "1_1") (pintype "passive"))
      (node (ref "C43") (pin "2") (pinfunction "-_2") (pintype "bidirectional"))
      (node (ref "C44") (pin "1") (pinfunction "1_1") (pintype "passive"))
      (node (ref "C45") (pin "2") (pinfunction "2_2") (pintype "passive"))
      (node (ref "C46") (pin "2") (pinfunction "2_2") (pintype "passive"))
      (node (ref "C47") (pin "1") (pinfunction "1_1") (pintype "passive"))
      (node (ref "C48") (pin "1") (pinfunction "1_1") (pintype "passive"))
      (node (ref "C49") (pin "2") (pinfunction "2_2") (pintype "passive"))
      (node (ref "C5") (pin "2") (pinfunction "2_2") (pintype "passive"))
      (node (ref "C50") (pin "2") (pinfunction "2_2") (pintype "passive"))
      (node (ref "C51") (pin "2") (pinfunction "2_2") (pintype "passive"))
      (node (ref "C52") (pin "2") (pinfunction "2_2") (pintype "passive"))
      (node (ref "C6") (pin "2") (pinfunction "2_2") (pintype "passive"))
      (node (ref "C7") (pin "2") (pinfunction "2_2") (pintype "passive"))
      (node (ref "C8") (pin "2") (pinfunction "2_2") (pintype "passive"))
      (node (ref "C9") (pin "2") (pinfunction "2_2") (pintype "passive"))
      (node (ref "GND") (pin "TP") (pinfunction "TP_TP") (pintype "input"))
      (node (ref "IC1") (pin "4") (pinfunction "GND_4") (pintype "bidirectional"))
      (node (ref "IC1") (pin "9") (pinfunction "EP_9") (pintype "bidirectional"))
      (node (ref "J1") (pin "2") (pinfunction "2_2") (pintype "passive"))
      (node (ref "J1") (pin "S1") (pinfunction "SHIELD_S1") (pintype "passive"))
      (node (ref "J1") (pin "S2") (pinfunction "SHIELD_S2") (pintype "passive"))
      (node (ref "J2") (pin "A1_B12") (pinfunction "GND_A1_B12") (pintype "power_in"))
      (node (ref "J2") (pin "B1_A12") (pinfunction "GND_B1_A12") (pintype "power_in"))
      (node (ref "J2") (pin "S1") (pinfunction "SHIELD_S1") (pintype "passive"))
      (node (ref "J2") (pin "S2") (pinfunction "SHIELD_S2") (pintype "passive"))
      (node (ref "J2") (pin "S3") (pinfunction "SHIELD_S3") (pintype "passive"))
      (node (ref "J2") (pin "S4") (pinfunction "SHIELD_S4") (pintype "passive"))
      (node (ref "J3") (pin "1") (pinfunction "1_1") (pintype "power_in"))
      (node (ref "L3") (pin "1") (pinfunction "1_1") (pintype "passive"))
      (node (ref "Q1") (pin "2") (pinfunction "S_2") (pintype "bidirectional"))
      (node (ref "Q2") (pin "2") (pinfunction "S_2") (pintype "bidirectional"))
      (node (ref "R10") (pin "1") (pinfunction "1_1") (pintype "passive"))
      (node (ref "R18") (pin "1") (pinfunction "1_1") (pintype "passive"))
      (node (ref "R2") (pin "2") (pinfunction "2_2") (pintype "passive"))
      (node (ref "R9") (pin "1") (pinfunction "1_1") (pintype "passive"))
      (node (ref "U$1") (pin "P$1") (pinfunction "GND_P$1") (pintype "power_in"))
      (node (ref "U$1") (pin "P$2") (pinfunction "GND_P$2") (pintype "power_in"))
      (node (ref "U$1") (pin "P$3") (pinfunction "GND_P$3") (pintype "power_in"))
      (node (ref "U$1") (pin "P$4") (pinfunction "GND_P$4") (pintype "power_in"))
      (node (ref "U$1") (pin "P6") (pinfunction "GND_P6") (pintype "power_in"))
      (node (ref "U1") (pin "47") (pinfunction "VREG_GND_47") (pintype "bidirectional"))
      (node (ref "U1") (pin "EPAD") (pinfunction "GND_EPAD") (pintype "bidirectional"))
      (node (ref "U10") (pin "4") (pinfunction "VSS_4") (pintype "power_in"))
      (node (ref "U11") (pin "P$3") (pinfunction "GND_P$3") (pintype "bidirectional"))
      (node (ref "U12") (pin "P$3") (pinfunction "GND_P$3") (pintype "bidirectional"))
      (node (ref "U13") (pin "P$3") (pinfunction "GND_P$3") (pintype "bidirectional"))
      (node (ref "U14") (pin "P$3") (pinfunction "GND_P$3") (pintype "bidirectional"))
      (node (ref "U15") (pin "2") (pinfunction "GND_2") (pintype "power_in"))
      (node (ref "U2") (pin "4") (pinfunction "VSS_4") (pintype "bidirectional"))
      (node (ref "U2") (pin "9") (pinfunction "VSS_9") (pintype "bidirectional"))
      (node (ref "U3") (pin "1") (pinfunction "GND_1") (pintype "power_in"))
      (node (ref "U3") (pin "11") (pinfunction "GND_11") (pintype "power_in"))
      (node (ref "U3") (pin "14") (pinfunction "GND_14") (pintype "power_in"))
      (node (ref "U3") (pin "2") (pinfunction "GND_2") (pintype "power_in"))
      (node (ref "U3") (pin "36") (pinfunction "GND_36") (pintype "power_in"))
      (node (ref "U3") (pin "37") (pinfunction "GND_37") (pintype "power_in"))
      (node (ref "U3") (pin "38") (pinfunction "GND_38") (pintype "power_in"))
      (node (ref "U3") (pin "39") (pinfunction "GND_39") (pintype "power_in"))
      (node (ref "U3") (pin "40") (pinfunction "GND_40") (pintype "power_in"))
      (node (ref "U3") (pin "41") (pinfunction "GND_41") (pintype "power_in"))
      (node (ref "U3") (pin "42") (pinfunction "GND_42") (pintype "power_in"))
      (node (ref "U3") (pin "43") (pinfunction "GND_43") (pintype "power_in"))
      (node (ref "U3") (pin "44") (pinfunction "GND_44") (pintype "power_in"))
      (node (ref "U3") (pin "45") (pinfunction "GND_45") (pintype "power_in"))
      (node (ref "U3") (pin "46") (pinfunction "GND_46") (pintype "power_in"))
      (node (ref "U3") (pin "47") (pinfunction "GND_47") (pintype "power_in"))
      (node (ref "U3") (pin "48") (pinfunction "GND_48") (pintype "power_in"))
      (node (ref "U3") (pin "49_1") (pinfunction "GND_49_1") (pintype "power_in"))
      (node (ref "U3") (pin "49_2") (pinfunction "GND_49_2") (pintype "power_in"))
      (node (ref "U3") (pin "49_3") (pinfunction "GND_49_3") (pintype "power_in"))
      (node (ref "U3") (pin "49_4") (pinfunction "GND_49_4") (pintype "power_in"))
      (node (ref "U3") (pin "49_5") (pinfunction "GND_49_5") (pintype "power_in"))
      (node (ref "U3") (pin "49_6") (pinfunction "GND_49_6") (pintype "power_in"))
      (node (ref "U3") (pin "49_7") (pinfunction "GND_49_7") (pintype "power_in"))
      (node (ref "U3") (pin "49_8") (pinfunction "GND_49_8") (pintype "power_in"))
      (node (ref "U3") (pin "49_9") (pinfunction "GND_49_9") (pintype "power_in"))
      (node (ref "U3") (pin "50") (pinfunction "GND_50") (pintype "power_in"))
      (node (ref "U3") (pin "51") (pinfunction "GND_51") (pintype "power_in"))
      (node (ref "U3") (pin "52") (pinfunction "GND_52") (pintype "power_in"))
      (node (ref "U3") (pin "53") (pinfunction "GND_53") (pintype "power_in"))
      (node (ref "U4") (pin "2") (pinfunction "GND_2") (pintype "power_in"))
      (node (ref "U5") (pin "1") (pinfunction "GND_1") (pintype "power_in"))
      (node (ref "U5") (pin "5") (pinfunction "SDO_5") (pintype "bidirectional"))
      (node (ref "U5") (pin "7") (pinfunction "GND_7") (pintype "power_in"))
      (node (ref "U6") (pin "P1") (pinfunction "GNDP_P1") (pintype "bidirectional"))
      (node (ref "U6") (pin "P10") (pinfunction "GNDP_P10") (pintype "bidirectional"))
      (node (ref "U6") (pin "P5") (pinfunction "GNDP_P5") (pintype "bidirectional"))
      (node (ref "U6") (pin "P7") (pinfunction "GNDP_P7") (pintype "bidirectional"))
      (node (ref "U7") (pin "4") (pinfunction "VSS_4") (pintype "power_in"))
      (node (ref "U7") (pin "5") (pinfunction "VSS_5") (pintype "power_in"))
      (node (ref "U8") (pin "5") (pinfunction "E(GND)_5") (pintype "passive"))
      (node (ref "U9") (pin "12") (pinfunction "MISO_12") (pintype "output"))
      (node (ref "U9") (pin "17") (pinfunction "EXP_17") (pintype "power_in"))
      (node (ref "U9") (pin "2") (pinfunction "INN_2") (pintype "bidirectional"))
      (node (ref "U9") (pin "4") (pinfunction "GND_4") (pintype "power_in"))
      (node (ref "U9") (pin "7") (pinfunction "EN_VREG_7") (pintype "input"))
      (node (ref "U9") (pin "8") (pinfunction "~{CS}_8") (pintype "input"))
      (node (ref "USR_BUTTON") (pin "3") (pinfunction "2_3") (pintype "passive"))
      (node (ref "USR_BUTTON") (pin "4") (pinfunction "2_4") (pintype "passive"))
      (node (ref "Y1") (pin "2") (pinfunction "GND_2") (pintype "power_in"))
      (node (ref "Y1") (pin "4") (pinfunction "GND_4") (pintype "power_in"))
    )
    (net (code "17") (name "GND-ISO") (class "Default")
      (node (ref "C37") (pin "2") (pinfunction "2_2") (pintype "passive"))
      (node (ref "C38") (pin "2") (pinfunction "2_2") (pintype "passive"))
      (node (ref "C39") (pin "2") (pinfunction "2_2") (pintype "passive"))
      (node (ref "C40") (pin "1") (pinfunction "1_1") (pintype "passive"))
      (node (ref "C41") (pin "1") (pinfunction "1_1") (pintype "passive"))
      (node (ref "R20") (pin "1") (pinfunction "1_1") (pintype "passive"))
      (node (ref "U$2") (pin "P$6") (pinfunction "GND_P$6") (pintype "power_in"))
      (node (ref "U$3") (pin "P$6") (pinfunction "GND_P$6") (pintype "power_in"))
      (node (ref "U6") (pin "P11") (pinfunction "GNDISO_P11") (pintype "bidirectional"))
      (node (ref "U6") (pin "P14") (pinfunction "GNDISO_P14") (pintype "bidirectional"))
      (node (ref "U6") (pin "P16") (pinfunction "GNDISO_P16") (pintype "bidirectional"))
      (node (ref "U6") (pin "P20") (pinfunction "GNDISO_P20") (pintype "bidirectional"))
      (node (ref "U8") (pin "2") (pinfunction "C1_2") (pintype "passive"))
      (node (ref "U8") (pin "3") (pinfunction "C2_3") (pintype "passive"))
    )
    (net (code "18") (name "INT_RTC") (class "Default")
      (node (ref "U1") (pin "40") (pinfunction "GPIO26/ADC0_40") (pintype "bidirectional"))
      (node (ref "U10") (pin "3") (pinfunction "~{INT}_3") (pintype "output"))
    )
    (net (code "19") (name "INT_SOIL") (class "Default")
      (node (ref "R14") (pin "1") (pinfunction "1_1") (pintype "passive"))
      (node (ref "U1") (pin "3") (pinfunction "GPIO1_3") (pintype "bidirectional"))
      (node (ref "U8") (pin "7") (pinfunction "C1(VO1)_7") (pintype "passive"))
    )
    (net (code "20") (name "INT_SOILTEMP") (class "Default")
      (node (ref "R15") (pin "1") (pinfunction "1_1") (pintype "passive"))
      (node (ref "U1") (pin "4") (pinfunction "GPIO2_4") (pintype "bidirectional"))
      (node (ref "U8") (pin "6") (pinfunction "C2(VO2)_6") (pintype "passive"))
    )
    (net (code "21") (name "INT_SOILTEMP_ISO") (class "Default")
      (node (ref "R16") (pin "1") (pinfunction "1_1") (pintype "passive"))
      (node (ref "U$3") (pin "P$7") (pinfunction "INT_P$7") (pintype "bidirectional"))
    )
    (net (code "22") (name "INT_SOIL_ISO") (class "Default")
      (node (ref "R17") (pin "1") (pinfunction "1_1") (pintype "passive"))
      (node (ref "U$2") (pin "P$7") (pinfunction "INT_P$7") (pintype "bidirectional"))
    )
    (net (code "23") (name "IRQ_LIGHTNING") (class "Default")
      (node (ref "U1") (pin "10") (pinfunction "GPIO7_10") (pintype "bidirectional"))
      (node (ref "U9") (pin "10") (pinfunction "IRQ_10") (pintype "output"))
    )
    (net (code "24") (name "NEOPIXEL_3.3V") (class "Default")
      (node (ref "U1") (pin "27") (pinfunction "GPIO16_27") (pintype "bidirectional"))
      (node (ref "U15") (pin "3") (pinfunction "A_3") (pintype "input"))
    )
    (net (code "25") (name "NEOPIXEL_5V") (class "Default")
      (node (ref "U11") (pin "P$4") (pinfunction "DI_P$4") (pintype "bidirectional"))
      (node (ref "U15") (pin "4") (pinfunction "B_4") (pintype "output"))
    )
    (net (code "26") (name "Net-(C21-Pad1)") (class "Default")
      (node (ref "C21") (pin "1") (pinfunction "1_1") (pintype "passive"))
      (node (ref "J2") (pin "A4_B9") (pinfunction "VBUS_A4_B9") (pintype "power_in"))
      (node (ref "J2") (pin "B4_A9") (pinfunction "VBUS_B4_A9") (pintype "power_in"))
      (node (ref "L2") (pin "1") (pinfunction "1_1") (pintype "passive"))
    )
    (net (code "27") (name "Net-(C43-+)") (class "Default")
      (node (ref "C43") (pin "1") (pinfunction "+_1") (pintype "bidirectional"))
      (node (ref "C46") (pin "1") (pinfunction "1_1") (pintype "passive"))
      (node (ref "D2") (pin "C") (pinfunction "C_C") (pintype "passive"))
      (node (ref "U10") (pin "8") (pinfunction "VDD_8") (pintype "power_in"))
    )
    (net (code "28") (name "Net-(J2-CC1)") (class "Default")
      (node (ref "J2") (pin "A5") (pinfunction "CC1_A5") (pintype "bidirectional"))
      (node (ref "R10") (pin "2") (pinfunction "2_2") (pintype "passive"))
    )
    (net (code "29") (name "Net-(J2-CC2)") (class "Default")
      (node (ref "J2") (pin "B5") (pinfunction "CC2_B5") (pintype "bidirectional"))
      (node (ref "R9") (pin "2") (pinfunction "2_2") (pintype "passive"))
    )
    (net (code "30") (name "Net-(Q2-D)") (class "Default")
      (node (ref "D1") (pin "A") (pinfunction "A_A") (pintype "passive"))
      (node (ref "LS1") (pin "N") (pinfunction "N_N") (pintype "passive"))
      (node (ref "Q2") (pin "3") (pinfunction "D_3") (pintype "bidirectional"))
    )
    (net (code "31") (name "Net-(Q2-G)") (class "Default")
      (node (ref "Q2") (pin "1") (pinfunction "G_1") (pintype "bidirectional"))
      (node (ref "R25") (pin "1") (pinfunction "1_1") (pintype "passive"))
    )
    (net (code "32") (name "Net-(R2-Pad1)") (class "Default")
      (node (ref "R2") (pin "1") (pinfunction "1_1") (pintype "passive"))
      (node (ref "RESET") (pin "3") (pinfunction "2_3") (pintype "passive"))
      (node (ref "RESET") (pin "4") (pinfunction "2_4") (pintype "passive"))
    )
    (net (code "33") (name "Net-(U1-GPIO3)") (class "Default")
      (node (ref "U1") (pin "5") (pinfunction "GPIO3_5") (pintype "bidirectional"))
      (node (ref "USR_BUTTON") (pin "1") (pinfunction "1_1") (pintype "passive"))
      (node (ref "USR_BUTTON") (pin "2") (pinfunction "1_2") (pintype "passive"))
    )
    (net (code "34") (name "Net-(U1-USB_D+)") (class "Default")
      (node (ref "R3") (pin "2") (pinfunction "2_2") (pintype "passive"))
      (node (ref "U1") (pin "52") (pinfunction "USB_D+_52") (pintype "bidirectional"))
    )
    (net (code "35") (name "Net-(U1-USB_D-)") (class "Default")
      (node (ref "R4") (pin "2") (pinfunction "2_2") (pintype "passive"))
      (node (ref "U1") (pin "51") (pinfunction "USB_D-_51") (pintype "bidirectional"))
    )
    (net (code "36") (name "Net-(U1-VREG_AVDD)") (class "Default")
      (node (ref "C10") (pin "1") (pinfunction "1_1") (pintype "passive"))
      (node (ref "R1") (pin "2") (pinfunction "2_2") (pintype "passive"))
      (node (ref "U1") (pin "46") (pinfunction "VREG_AVDD_46") (pintype "bidirectional"))
    )
    (net (code "37") (name "Net-(U1-VREG_LX)") (class "Default")
      (node (ref "L1") (pin "1") (pinfunction "1_1") (pintype "passive"))
      (node (ref "U1") (pin "48") (pinfunction "VREG_LX_48") (pintype "bidirectional"))
    )
    (net (code "38") (name "Net-(U1-XIN)") (class "Default")
      (node (ref "C19") (pin "1") (pinfunction "1_1") (pintype "passive"))
      (node (ref "U1") (pin "21") (pinfunction "XIN_21") (pintype "bidirectional"))
      (node (ref "Y1") (pin "1") (pinfunction "1_1") (pintype "passive"))
    )
    (net (code "39") (name "Net-(U1-XOUT)") (class "Default")
      (node (ref "R8") (pin "2") (pinfunction "2_2") (pintype "passive"))
      (node (ref "U1") (pin "22") (pinfunction "XOUT_22") (pintype "bidirectional"))
    )
    (net (code "40") (name "Net-(U3-IO8)") (class "Default")
      (node (ref "R13") (pin "1") (pinfunction "1_1") (pintype "passive"))
      (node (ref "U3") (pin "22") (pinfunction "IO8_22") (pintype "bidirectional"))
    )
    (net (code "41") (name "Net-(U6-VSEL)") (class "Default")
      (node (ref "R19") (pin "1") (pinfunction "1_1") (pintype "passive"))
      (node (ref "R20") (pin "2") (pinfunction "2_2") (pintype "passive"))
      (node (ref "U6") (pin "P13") (pinfunction "VSEL_P13") (pintype "bidirectional"))
    )
    (net (code "42") (name "Net-(U8-A1)") (class "Default")
      (node (ref "R17") (pin "2") (pinfunction "2_2") (pintype "passive"))
      (node (ref "U8") (pin "1") (pinfunction "A1_1") (pintype "passive"))
    )
    (net (code "43") (name "Net-(U8-A2)") (class "Default")
      (node (ref "R16") (pin "2") (pinfunction "2_2") (pintype "passive"))
      (node (ref "U8") (pin "4") (pinfunction "A2_4") (pintype "passive"))
    )
    (net (code "44") (name "Net-(U9-ACG)") (class "Default")
      (node (ref "C31") (pin "1") (pinfunction "1_1") (pintype "passive"))
      (node (ref "U9") (pin "1") (pinfunction "ACG_1") (pintype "passive"))
    )
    (net (code "45") (name "Net-(U9-INP)") (class "Default")
      (node (ref "C33") (pin "1") (pinfunction "1_1") (pintype "passive"))
      (node (ref "L3") (pin "2") (pinfunction "2_2") (pintype "passive"))
      (node (ref "R18") (pin "2") (pinfunction "2_2") (pintype "passive"))
      (node (ref "U9") (pin "3") (pinfunction "INP_3") (pintype "bidirectional"))
    )
    (net (code "46") (name "Net-(U10-OSCI)") (class "Default")
      (node (ref "C47") (pin "2") (pinfunction "2_2") (pintype "passive"))
      (node (ref "U10") (pin "1") (pinfunction "OSCI_1") (pintype "input"))
      (node (ref "XTAL1") (pin "2") (pinfunction "2_2") (pintype "passive"))
    )
    (net (code "47") (name "Net-(U10-OSCO)") (class "Default")
      (node (ref "C48") (pin "2") (pinfunction "2_2") (pintype "passive"))
      (node (ref "U10") (pin "2") (pinfunction "OSCO_2") (pintype "output"))
      (node (ref "XTAL1") (pin "1") (pinfunction "1_1") (pintype "passive"))
    )
    (net (code "48") (name "Net-(U11-DO)") (class "Default")
      (node (ref "U11") (pin "P$2") (pinfunction "DO_P$2") (pintype "bidirectional"))
      (node (ref "U12") (pin "P$4") (pinfunction "DI_P$4") (pintype "bidirectional"))
    )
    (net (code "49") (name "Net-(U12-DO)") (class "Default")
      (node (ref "U12") (pin "P$2") (pinfunction "DO_P$2") (pintype "bidirectional"))
      (node (ref "U13") (pin "P$4") (pinfunction "DI_P$4") (pintype "bidirectional"))
    )
    (net (code "50") (name "Net-(U13-DO)") (class "Default")
      (node (ref "U13") (pin "P$2") (pinfunction "DO_P$2") (pintype "bidirectional"))
      (node (ref "U14") (pin "P$4") (pinfunction "DI_P$4") (pintype "bidirectional"))
    )
    (net (code "51") (name "Net-(Y1-2)") (class "Default")
      (node (ref "C18") (pin "1") (pinfunction "1_1") (pintype "passive"))
      (node (ref "R8") (pin "1") (pinfunction "1_1") (pintype "passive"))
      (node (ref "Y1") (pin "3") (pinfunction "2_3") (pintype "passive"))
    )
    (net (code "52") (name "PDIS") (class "Default")
      (node (ref "Q1") (pin "3") (pinfunction "D_3") (pintype "bidirectional"))
      (node (ref "R23") (pin "1") (pinfunction "1_1") (pintype "passive"))
      (node (ref "U6") (pin "P8") (pinfunction "PDIS_P8") (pintype "bidirectional"))
    )
    (net (code "53") (name "PDIS_EN") (class "Default")
      (node (ref "Q1") (pin "1") (pinfunction "G_1") (pintype "bidirectional"))
      (node (ref "R24") (pin "1") (pinfunction "1_1") (pintype "passive"))
      (node (ref "U1") (pin "12") (pinfunction "GPIO8_12") (pintype "bidirectional"))
    )
    (net (code "54") (name "PRB1") (class "Default")
      (node (ref "J4") (pin "1") (pinfunction "1_1") (pintype "passive"))
      (node (ref "U$2") (pin "P$4") (pinfunction "PRB_P$4") (pintype "bidirectional"))
    )
    (net (code "55") (name "PRB1_GND") (class "Default")
      (node (ref "J4") (pin "2") (pinfunction "2_2") (pintype "passive"))
      (node (ref "J4") (pin "3") (pinfunction "2_3") (pintype "passive"))
      (node (ref "U$2") (pin "P$5") (pinfunction "PRB_GND_P$5") (pintype "bidirectional"))
    )
    (net (code "56") (name "PROBE2") (class "Default")
      (node (ref "J5") (pin "1") (pinfunction "1_1") (pintype "passive"))
      (node (ref "U$3") (pin "P$4") (pinfunction "PRB_P$4") (pintype "bidirectional"))
    )
    (net (code "57") (name "PROBE2_GND") (class "Default")
      (node (ref "J5") (pin "2") (pinfunction "2_2") (pintype "passive"))
      (node (ref "J5") (pin "3") (pinfunction "2_3") (pintype "passive"))
      (node (ref "U$3") (pin "P$5") (pinfunction "PRB_GND_P$5") (pintype "bidirectional"))
    )
    (net (code "58") (name "QSPI_CLK") (class "Default")
      (node (ref "IC1") (pin "6") (pinfunction "CLK_6") (pintype "bidirectional"))
      (node (ref "U1") (pin "56") (pinfunction "QSPI_SCLK_56") (pintype "bidirectional"))
      (node (ref "U2") (pin "6") (pinfunction "SCLK_6") (pintype "bidirectional"))
    )
    (net (code "59") (name "SCL") (class "Default")
      (node (ref "J3") (pin "4") (pinfunction "4_4") (pintype "passive"))
      (node (ref "R12") (pin "1") (pinfunction "1_1") (pintype "passive"))
      (node (ref "U1") (pin "37") (pinfunction "GPIO25_37") (pintype "bidirectional"))
      (node (ref "U10") (pin "6") (pinfunction "SCL_6") (pintype "input"))
      (node (ref "U5") (pin "4") (pinfunction "SCK_4") (pintype "input"))
      (node (ref "U6") (pin "P2") (pinfunction "SCL2_P2") (pintype "bidirectional"))
      (node (ref "U7") (pin "2") (pinfunction "SCL_2") (pintype "input"))
      (node (ref "U9") (pin "11") (pinfunction "I2CL/SCL_11") (pintype "input"))
    )
    (net (code "60") (name "SCL_ISO") (class "Default")
      (node (ref "R22") (pin "1") (pinfunction "1_1") (pintype "passive"))
      (node (ref "U$2") (pin "P$8") (pinfunction "SCL_P$8") (pintype "bidirectional"))
      (node (ref "U$3") (pin "P$8") (pinfunction "SCL_P$8") (pintype "bidirectional"))
      (node (ref "U6") (pin "P19") (pinfunction "SCL1_P19") (pintype "bidirectional"))
    )
    (net (code "61") (name "SDA") (class "Default")
      (node (ref "J3") (pin "3") (pinfunction "3_3") (pintype "passive"))
      (node (ref "R11") (pin "1") (pinfunction "1_1") (pintype "passive"))
      (node (ref "U1") (pin "36") (pinfunction "GPIO24_36") (pintype "bidirectional"))
      (node (ref "U10") (pin "5") (pinfunction "SDA_5") (pintype "bidirectional"))
      (node (ref "U5") (pin "3") (pinfunction "SDI_3") (pintype "bidirectional"))
      (node (ref "U6") (pin "P3") (pinfunction "SDA2_P3") (pintype "bidirectional"))
      (node (ref "U7") (pin "3") (pinfunction "SDA_3") (pintype "bidirectional"))
      (node (ref "U9") (pin "13") (pinfunction "I2CD/MOSI_13") (pintype "bidirectional"))
    )
    (net (code "62") (name "SDA_ISO") (class "Default")
      (node (ref "R21") (pin "1") (pinfunction "1_1") (pintype "passive"))
      (node (ref "U$2") (pin "P$1") (pinfunction "SDA_P$1") (pintype "bidirectional"))
      (node (ref "U$3") (pin "P$1") (pinfunction "SDA_P$1") (pintype "bidirectional"))
      (node (ref "U6") (pin "P18") (pinfunction "SDA1_P18") (pintype "bidirectional"))
    )
    (net (code "63") (name "SD_CLK") (class "Default")
      (node (ref "U$1") (pin "P5") (pinfunction "CLK_P5") (pintype "bidirectional"))
      (node (ref "U1") (pin "18") (pinfunction "GPIO14_18") (pintype "bidirectional"))
    )
    (net (code "64") (name "SIO0") (class "Default")
      (node (ref "IC1") (pin "5") (pinfunction "DI(IO0)_5") (pintype "bidirectional"))
      (node (ref "U1") (pin "57") (pinfunction "QSPI_SD0_57") (pintype "bidirectional"))
      (node (ref "U2") (pin "5") (pinfunction "SI/SIO0_5") (pintype "bidirectional"))
    )
    (net (code "65") (name "SIO1") (class "Default")
      (node (ref "IC1") (pin "2") (pinfunction "DO(IO1)_2") (pintype "bidirectional"))
      (node (ref "U1") (pin "59") (pinfunction "QSPI_SD1_59") (pintype "bidirectional"))
      (node (ref "U2") (pin "2") (pinfunction "SO/SIO1_2") (pintype "bidirectional"))
    )
    (net (code "66") (name "SIO2") (class "Default")
      (node (ref "IC1") (pin "3") (pinfunction "~{WP(IO2})_3") (pintype "bidirectional"))
      (node (ref "U1") (pin "58") (pinfunction "QSPI_SD2_58") (pintype "bidirectional"))
      (node (ref "U2") (pin "3") (pinfunction "SIO2_3") (pintype "bidirectional"))
    )
    (net (code "67") (name "SIO3") (class "Default")
      (node (ref "IC1") (pin "7") (pinfunction "~{HOLD_OR_}RESET_(IO3)_7") (pintype "bidirectional"))
      (node (ref "U1") (pin "55") (pinfunction "QSPI_SD3_55") (pintype "bidirectional"))
      (node (ref "U2") (pin "7") (pinfunction "SIO3_7") (pintype "bidirectional"))
    )
    (net (code "68") (name "SWCLK") (class "Default")
      (node (ref "J1") (pin "1") (pinfunction "1_1") (pintype "passive"))
      (node (ref "U1") (pin "24") (pinfunction "SWCLK_24") (pintype "bidirectional"))
    )
    (net (code "69") (name "SWDIO") (class "Default")
      (node (ref "J1") (pin "3") (pinfunction "3_3") (pintype "passive"))
      (node (ref "U1") (pin "25") (pinfunction "SWDIO_25") (pintype "bidirectional"))
    )
    (net (code "70") (name "SWITCH") (class "Default")
      (node (ref "U$1") (pin "G1") (pinfunction "SWITCH_G1") (pintype "bidirectional"))
      (node (ref "U1") (pin "13") (pinfunction "GPIO9_13") (pintype "bidirectional"))
    )
    (net (code "71") (name "USB_N") (class "Default")
      (node (ref "J2") (pin "A7") (pinfunction "DN1_A7") (pintype "bidirectional"))
      (node (ref "J2") (pin "B7") (pinfunction "DN2_B7") (pintype "bidirectional"))
      (node (ref "R4") (pin "1") (pinfunction "1_1") (pintype "passive"))
    )
    (net (code "72") (name "USB_P") (class "Default")
      (node (ref "J2") (pin "A6") (pinfunction "DP1_A6") (pintype "bidirectional"))
      (node (ref "J2") (pin "B6") (pinfunction "DP2_B6") (pintype "bidirectional"))
      (node (ref "R3") (pin "1") (pinfunction "1_1") (pintype "passive"))
    )
    (net (code "73") (name "VCC-ISO") (class "Default")
      (node (ref "C37") (pin "1") (pinfunction "1_1") (pintype "passive"))
      (node (ref "C38") (pin "1") (pinfunction "1_1") (pintype "passive"))
      (node (ref "C39") (pin "1") (pinfunction "1_1") (pintype "passive"))
      (node (ref "C40") (pin "2") (pinfunction "2_2") (pintype "passive"))
      (node (ref "C41") (pin "2") (pinfunction "2_2") (pintype "passive"))
      (node (ref "R19") (pin "2") (pinfunction "2_2") (pintype "passive"))
      (node (ref "R21") (pin "2") (pinfunction "2_2") (pintype "passive"))
      (node (ref "R22") (pin "2") (pinfunction "2_2") (pintype "passive"))
      (node (ref "U$2") (pin "P$3") (pinfunction "VCC_P$3") (pintype "power_in"))
      (node (ref "U$3") (pin "P$3") (pinfunction "VCC_P$3") (pintype "power_in"))
      (node (ref "U6") (pin "P12") (pinfunction "VISO_P12") (pintype "bidirectional"))
      (node (ref "U6") (pin "P17") (pinfunction "VDDISO_P17") (pintype "bidirectional"))
    )
    (net (code "74") (name "V_USB") (class "Default")
      (node (ref "C22") (pin "1") (pinfunction "1_1") (pintype "passive"))
      (node (ref "C23") (pin "2") (pinfunction "2_2") (pintype "passive"))
      (node (ref "C34") (pin "2") (pinfunction "2_2") (pintype "passive"))
      (node (ref "C35") (pin "2") (pinfunction "2_2") (pintype "passive"))
      (node (ref "C45") (pin "1") (pinfunction "1_1") (pintype "passive"))
      (node (ref "C49") (pin "1") (pinfunction "1_1") (pintype "passive"))
      (node (ref "C50") (pin "1") (pinfunction "1_1") (pintype "passive"))
      (node (ref "C51") (pin "1") (pinfunction "1_1") (pintype "passive"))
      (node (ref "C52") (pin "1") (pinfunction "1_1") (pintype "passive"))
      (node (ref "L2") (pin "2") (pinfunction "2_2") (pintype "passive"))
      (node (ref "R23") (pin "2") (pinfunction "2_2") (pintype "passive"))
      (node (ref "U11") (pin "P$1") (pinfunction "VCC_P$1") (pintype "bidirectional"))
      (node (ref "U12") (pin "P$1") (pinfunction "VCC_P$1") (pintype "bidirectional"))
      (node (ref "U13") (pin "P$1") (pinfunction "VCC_P$1") (pintype "bidirectional"))
      (node (ref "U14") (pin "P$1") (pinfunction "VCC_P$1") (pintype "bidirectional"))
      (node (ref "U15") (pin "6") (pinfunction "VCCB_6") (pintype "power_in"))
      (node (ref "U4") (pin "1") (pinfunction "VIN_1") (pintype "input"))
      (node (ref "U4") (pin "3") (pinfunction "EN_3") (pintype "input"))
      (node (ref "U6") (pin "P9") (pinfunction "VIN_P9") (pintype "bidirectional"))
      (node (ref "USB") (pin "TP") (pinfunction "TP_TP") (pintype "input"))
    )
    (net (code "75") (name "unconnected-(J2-SBU1-PadA8)") (class "Default")
      (node (ref "J2") (pin "A8") (pinfunction "SBU1_A8") (pintype "bidirectional"))
    )
    (net (code "76") (name "unconnected-(J2-SBU2-PadB8)") (class "Default")
      (node (ref "J2") (pin "B8") (pinfunction "SBU2_B8") (pintype "bidirectional"))
    )
    (net (code "77") (name "unconnected-(J6-Pad01)") (class "Default")
      (node (ref "J6") (pin "01") (pinfunction "01_01") (pintype "passive"))
    )
    (net (code "78") (name "unconnected-(J6-Pad02)") (class "Default")
      (node (ref "J6") (pin "02") (pinfunction "02_02") (pintype "passive"))
    )
    (net (code "79") (name "unconnected-(U$2-NC-PadP$2)") (class "Default")
      (node (ref "U$2") (pin "P$2") (pinfunction "NC_P$2") (pintype "no_connect"))
    )
    (net (code "80") (name "unconnected-(U$2-NC-PadP$9)") (class "Default")
      (node (ref "U$2") (pin "P$9") (pinfunction "NC_P$9") (pintype "no_connect"))
    )
    (net (code "81") (name "unconnected-(U$2-NC-PadP$10)") (class "Default")
      (node (ref "U$2") (pin "P$10") (pinfunction "NC_P$10") (pintype "no_connect"))
    )
    (net (code "82") (name "unconnected-(U$3-NC-PadP$2)") (class "Default")
      (node (ref "U$3") (pin "P$2") (pinfunction "NC_P$2") (pintype "no_connect"))
    )
    (net (code "83") (name "unconnected-(U$3-NC-PadP$9)") (class "Default")
      (node (ref "U$3") (pin "P$9") (pinfunction "NC_P$9") (pintype "no_connect"))
    )
    (net (code "84") (name "unconnected-(U$3-NC-PadP$10)") (class "Default")
      (node (ref "U$3") (pin "P$10") (pinfunction "NC_P$10") (pintype "no_connect"))
    )
    (net (code "85") (name "unconnected-(U1-GPIO27{slash}ADC1-Pad41)") (class "Default")
      (node (ref "U1") (pin "41") (pinfunction "GPIO27/ADC1_41") (pintype "bidirectional"))
    )
    (net (code "86") (name "unconnected-(U1-GPIO28{slash}ADC2-Pad42)") (class "Default")
      (node (ref "U1") (pin "42") (pinfunction "GPIO28/ADC2_42") (pintype "bidirectional"))
    )
    (net (code "87") (name "unconnected-(U1-GPIO29{slash}ADC3-Pad43)") (class "Default")
      (node (ref "U1") (pin "43") (pinfunction "GPIO29/ADC3_43") (pintype "bidirectional"))
    )
    (net (code "88") (name "unconnected-(U3-IO0-Pad12)") (class "Default")
      (node (ref "U3") (pin "12") (pinfunction "IO0_12") (pintype "bidirectional"))
    )
    (net (code "89") (name "unconnected-(U3-IO1-Pad13)") (class "Default")
      (node (ref "U3") (pin "13") (pinfunction "IO1_13") (pintype "bidirectional"))
    )
    (net (code "90") (name "unconnected-(U3-IO4-Pad18)") (class "Default")
      (node (ref "U3") (pin "18") (pinfunction "IO4_18") (pintype "bidirectional"))
    )
    (net (code "91") (name "unconnected-(U3-IO5-Pad19)") (class "Default")
      (node (ref "U3") (pin "19") (pinfunction "IO5_19") (pintype "bidirectional"))
    )
    (net (code "92") (name "unconnected-(U3-IO18-Pad26)") (class "Default")
      (node (ref "U3") (pin "26") (pinfunction "IO18_26") (pintype "bidirectional"))
    )
    (net (code "93") (name "unconnected-(U3-IO19-Pad27)") (class "Default")
      (node (ref "U3") (pin "27") (pinfunction "IO19_27") (pintype "bidirectional"))
    )
    (net (code "94") (name "unconnected-(U3-NC-Pad4)") (class "Default")
      (node (ref "U3") (pin "4") (pinfunction "NC_4") (pintype "no_connect"))
    )
    (net (code "95") (name "unconnected-(U3-NC-Pad7)") (class "Default")
      (node (ref "U3") (pin "7") (pinfunction "NC_7") (pintype "no_connect"))
    )
    (net (code "96") (name "unconnected-(U3-NC-Pad9)") (class "Default")
      (node (ref "U3") (pin "9") (pinfunction "NC_9") (pintype "no_connect"))
    )
    (net (code "97") (name "unconnected-(U3-NC-Pad10)") (class "Default")
      (node (ref "U3") (pin "10") (pinfunction "NC_10") (pintype "no_connect"))
    )
    (net (code "98") (name "unconnected-(U3-NC-Pad15)") (class "Default")
      (node (ref "U3") (pin "15") (pinfunction "NC_15") (pintype "no_connect"))
    )
    (net (code "99") (name "unconnected-(U3-NC-Pad17)") (class "Default")
      (node (ref "U3") (pin "17") (pinfunction "NC_17") (pintype "no_connect"))
    )
    (net (code "100") (name "unconnected-(U3-NC-Pad24)") (class "Default")
      (node (ref "U3") (pin "24") (pinfunction "NC_24") (pintype "no_connect"))
    )
    (net (code "101") (name "unconnected-(U3-NC-Pad25)") (class "Default")
      (node (ref "U3") (pin "25") (pinfunction "NC_25") (pintype "no_connect"))
    )
    (net (code "102") (name "unconnected-(U3-NC-Pad28)") (class "Default")
      (node (ref "U3") (pin "28") (pinfunction "NC_28") (pintype "no_connect"))
    )
    (net (code "103") (name "unconnected-(U3-NC-Pad29)") (class "Default")
      (node (ref "U3") (pin "29") (pinfunction "NC_29") (pintype "no_connect"))
    )
    (net (code "104") (name "unconnected-(U3-NC-Pad32)") (class "Default")
      (node (ref "U3") (pin "32") (pinfunction "NC_32") (pintype "no_connect"))
    )
    (net (code "105") (name "unconnected-(U3-NC-Pad33)") (class "Default")
      (node (ref "U3") (pin "33") (pinfunction "NC_33") (pintype "no_connect"))
    )
    (net (code "106") (name "unconnected-(U3-NC-Pad34)") (class "Default")
      (node (ref "U3") (pin "34") (pinfunction "NC_34") (pintype "no_connect"))
    )
    (net (code "107") (name "unconnected-(U3-NC-Pad35)") (class "Default")
      (node (ref "U3") (pin "35") (pinfunction "NC_35") (pintype "no_connect"))
    )
    (net (code "108") (name "unconnected-(U9-NC-Pad14)") (class "Default")
      (node (ref "U9") (pin "14") (pinfunction "NC_14") (pintype "no_connect"))
    )
    (net (code "109") (name "unconnected-(U10-CLKOUT-Pad7)") (class "Default")
      (node (ref "U10") (pin "7") (pinfunction "CLKOUT_7") (pintype "output"))
    )
    (net (code "110") (name "unconnected-(U14-DO-PadP$2)") (class "Default")
      (node (ref "U14") (pin "P$2") (pinfunction "DO_P$2") (pintype "bidirectional"))
    )
    (net (code "111") (name "~{ESP32_BOOT}") (class "Default")
      (node (ref "U1") (pin "31") (pinfunction "GPIO19_31") (pintype "bidirectional"))
      (node (ref "U3") (pin "23") (pinfunction "IO9_23") (pintype "bidirectional"))
    )
    (net (code "112") (name "~{ESP32_RST}") (class "Default")
      (node (ref "U1") (pin "29") (pinfunction "GPIO18_29") (pintype "bidirectional"))
      (node (ref "U3") (pin "8") (pinfunction "EN_8") (pintype "input"))
    )
    (net (code "113") (name "~{FLASH_CS}") (class "Default")
      (node (ref "R7") (pin "2") (pinfunction "2_2") (pintype "passive"))
      (node (ref "U1") (pin "2") (pinfunction "GPIO0_2") (pintype "bidirectional"))
      (node (ref "U2") (pin "1") (pinfunction "~{CE}_1") (pintype "bidirectional"))
    )
    (net (code "114") (name "~{QSPI_CS}") (class "Default")
      (node (ref "IC1") (pin "1") (pinfunction "~{CS}_1") (pintype "bidirectional"))
      (node (ref "R5") (pin "1") (pinfunction "1_1") (pintype "passive"))
      (node (ref "R6") (pin "2") (pinfunction "2_2") (pintype "passive"))
      (node (ref "U1") (pin "60") (pinfunction "QSPI_~{CS}_60") (pintype "bidirectional"))
    )
    (net (code "115") (name "~{RESET}") (class "Default")
      (node (ref "RESET") (pin "1") (pinfunction "1_1") (pintype "passive"))
      (node (ref "RESET") (pin "2") (pinfunction "1_2") (pintype "passive"))
      (node (ref "U1") (pin "26") (pinfunction "RUN_26") (pintype "bidirectional"))
    )
    (net (code "116") (name "~{USB_BOOT}") (class "Default")
      (node (ref "!BOOT") (pin "3") (pinfunction "2_3") (pintype "passive"))
      (node (ref "!BOOT") (pin "4") (pinfunction "2_4") (pintype "passive"))
      (node (ref "R6") (pin "1") (pinfunction "1_1") (pintype "passive"))
    )
  )
)
